# transponder-11_3_0.net
KiCad netlist of a schematic drawn in EAGLE
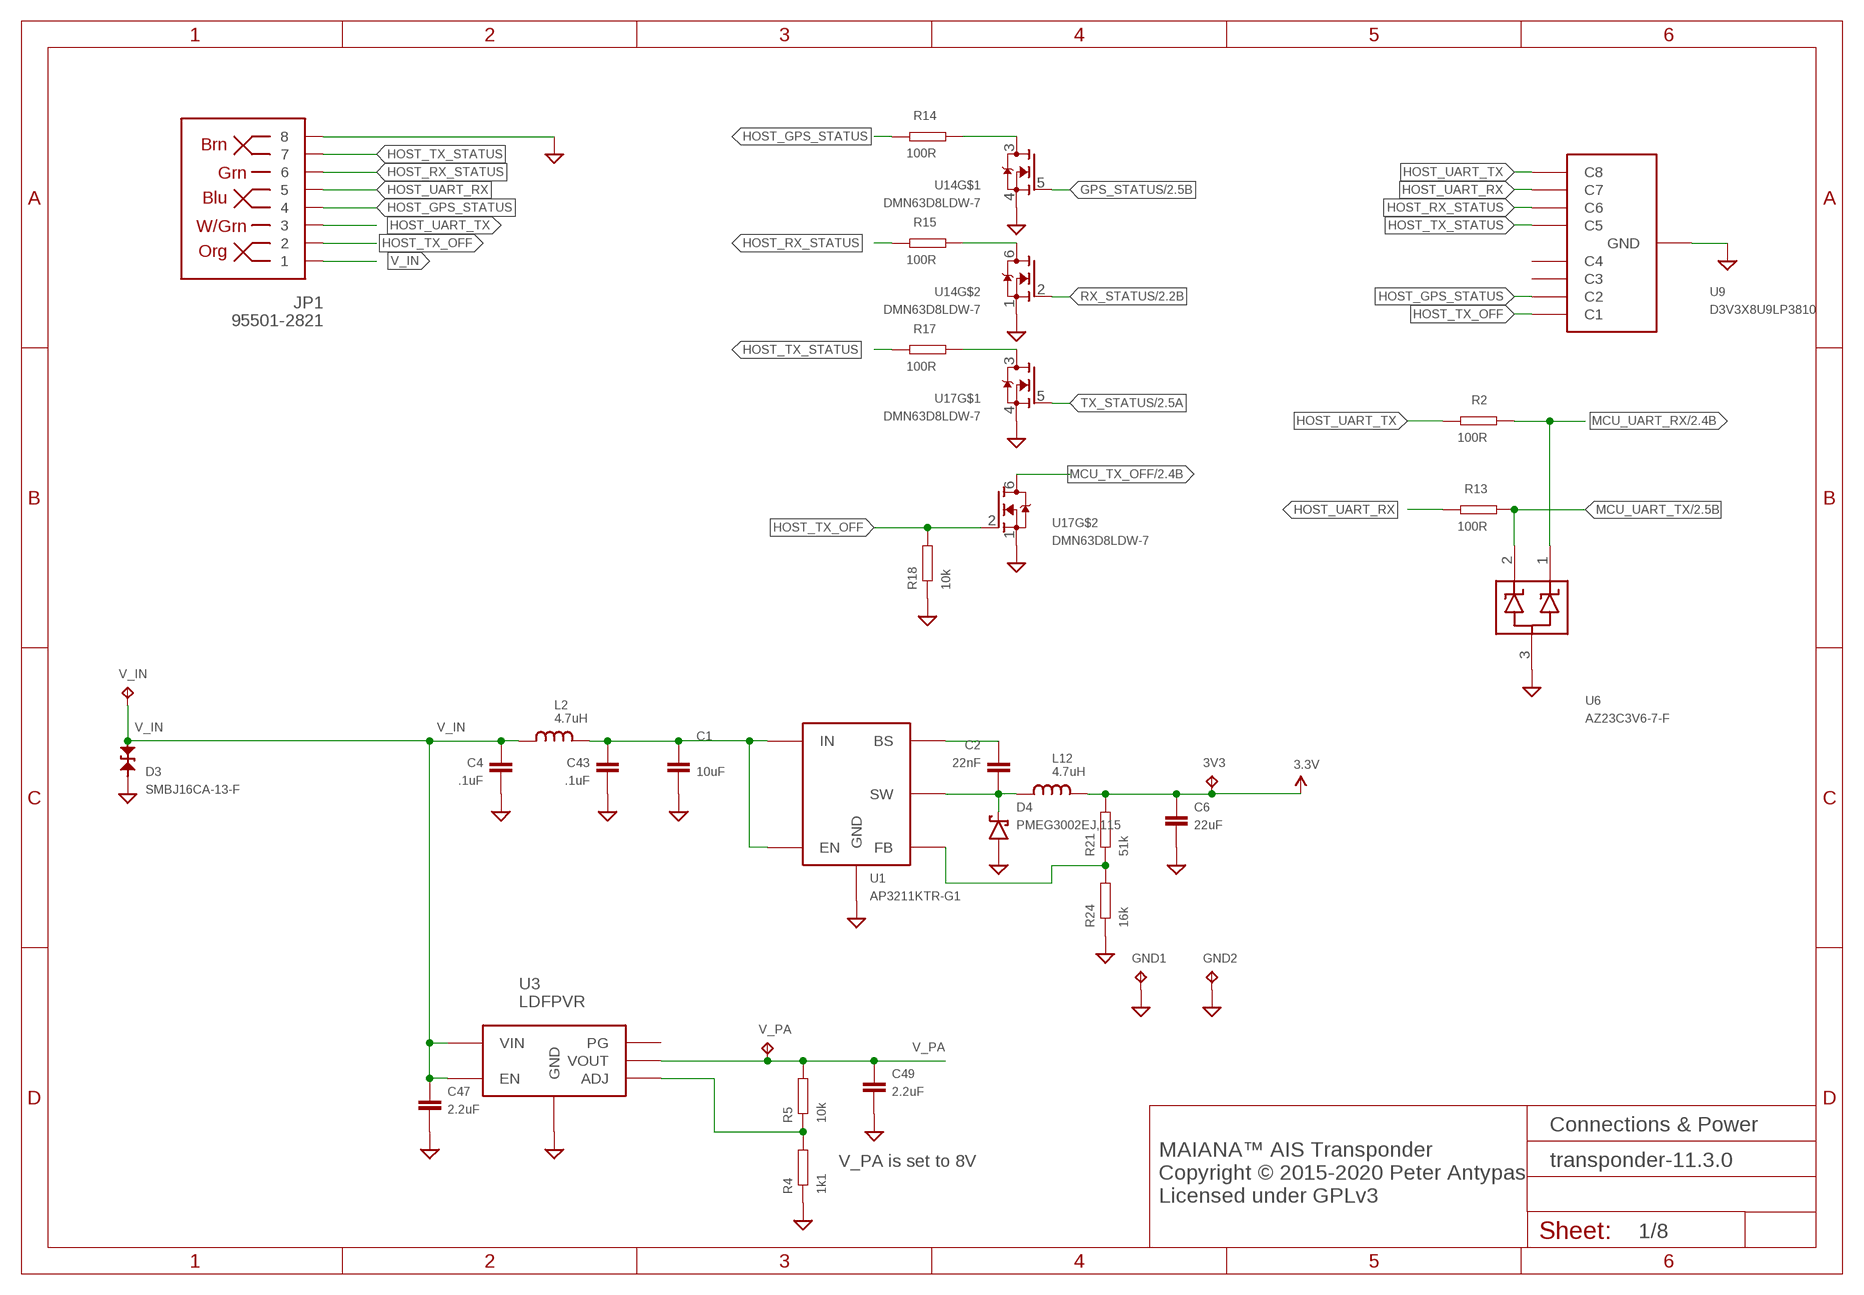
[diagram p0: schematic, sheet 1]
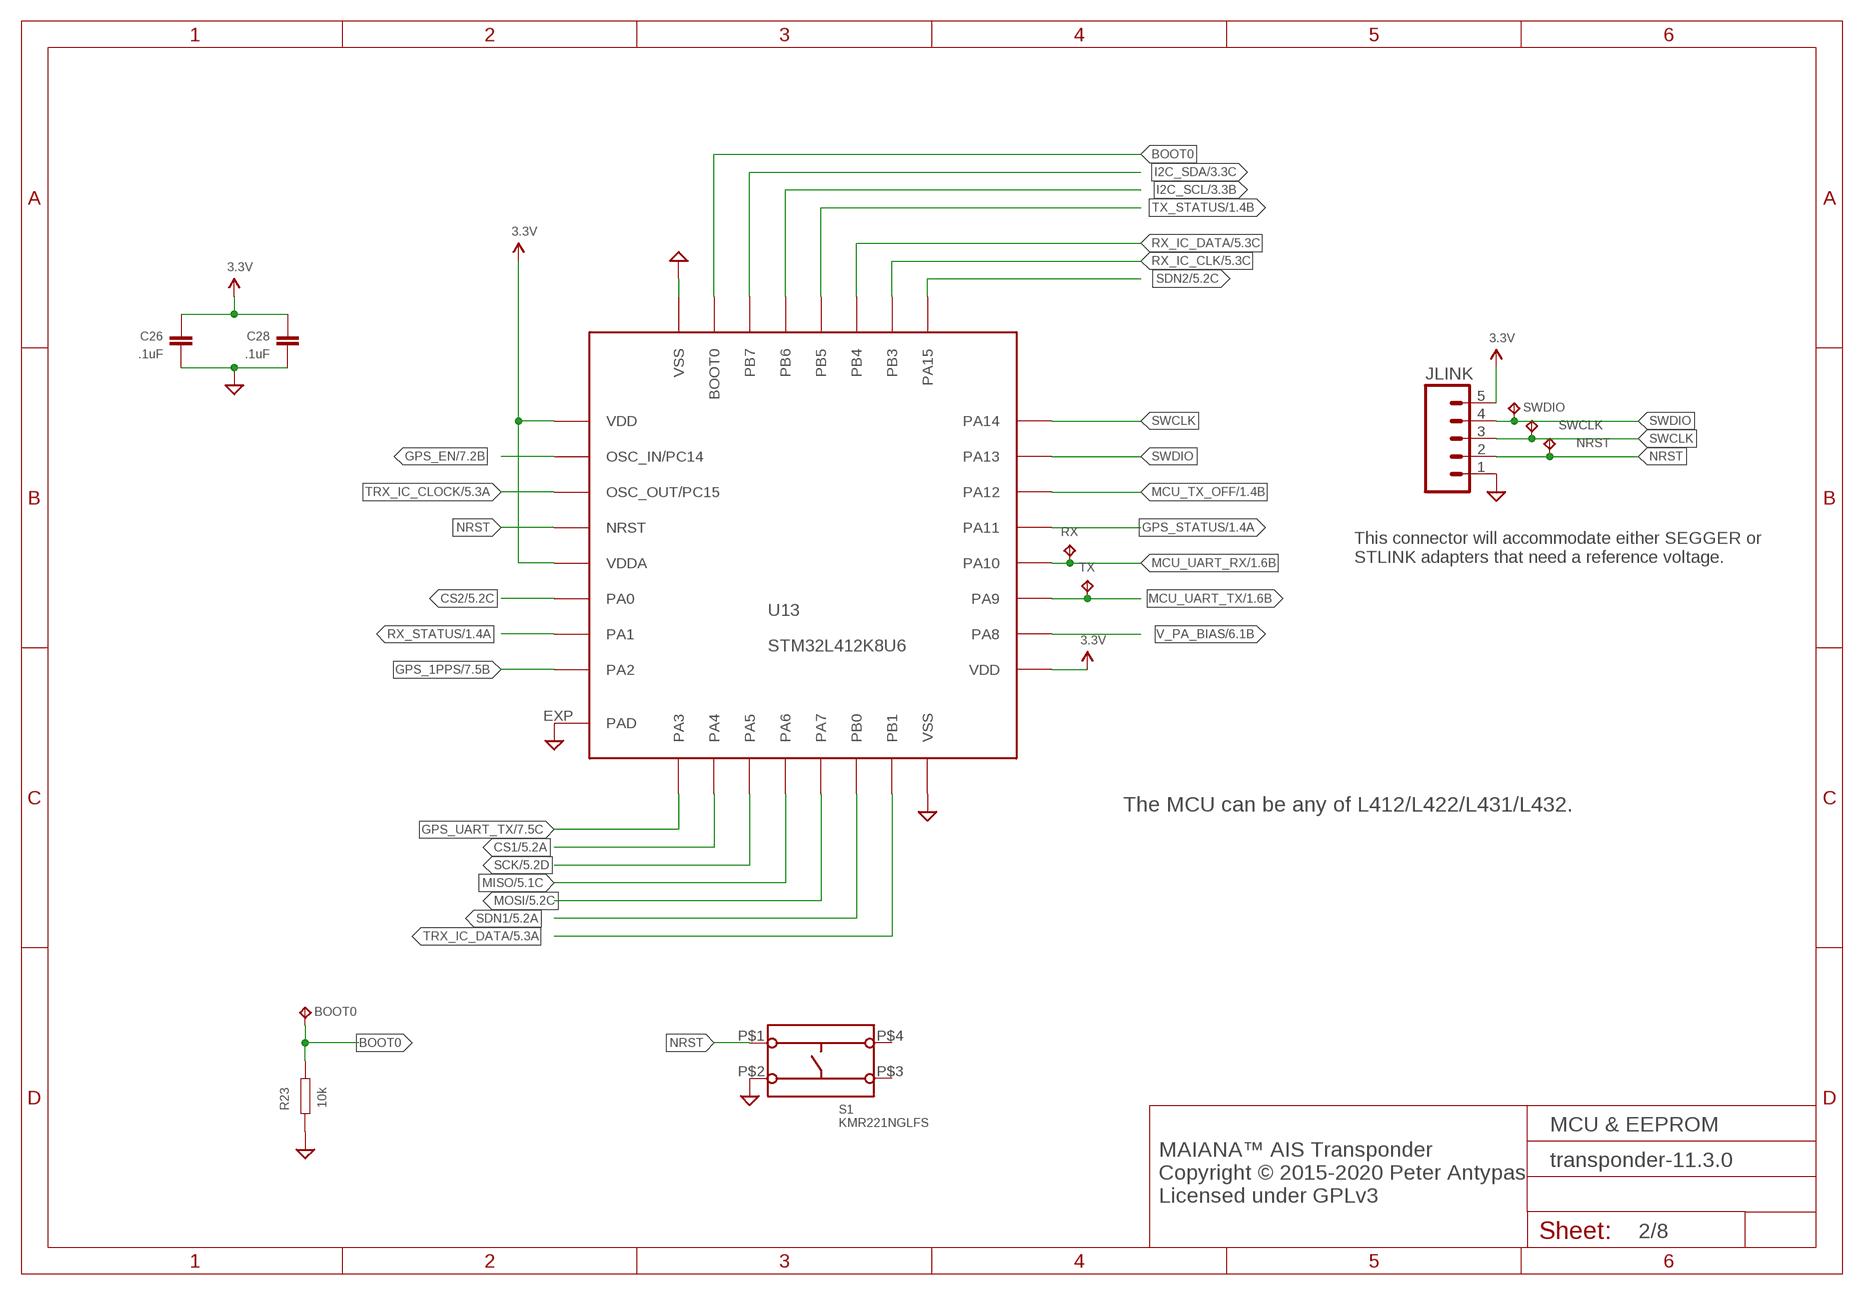
[diagram p1: schematic, sheet 2]
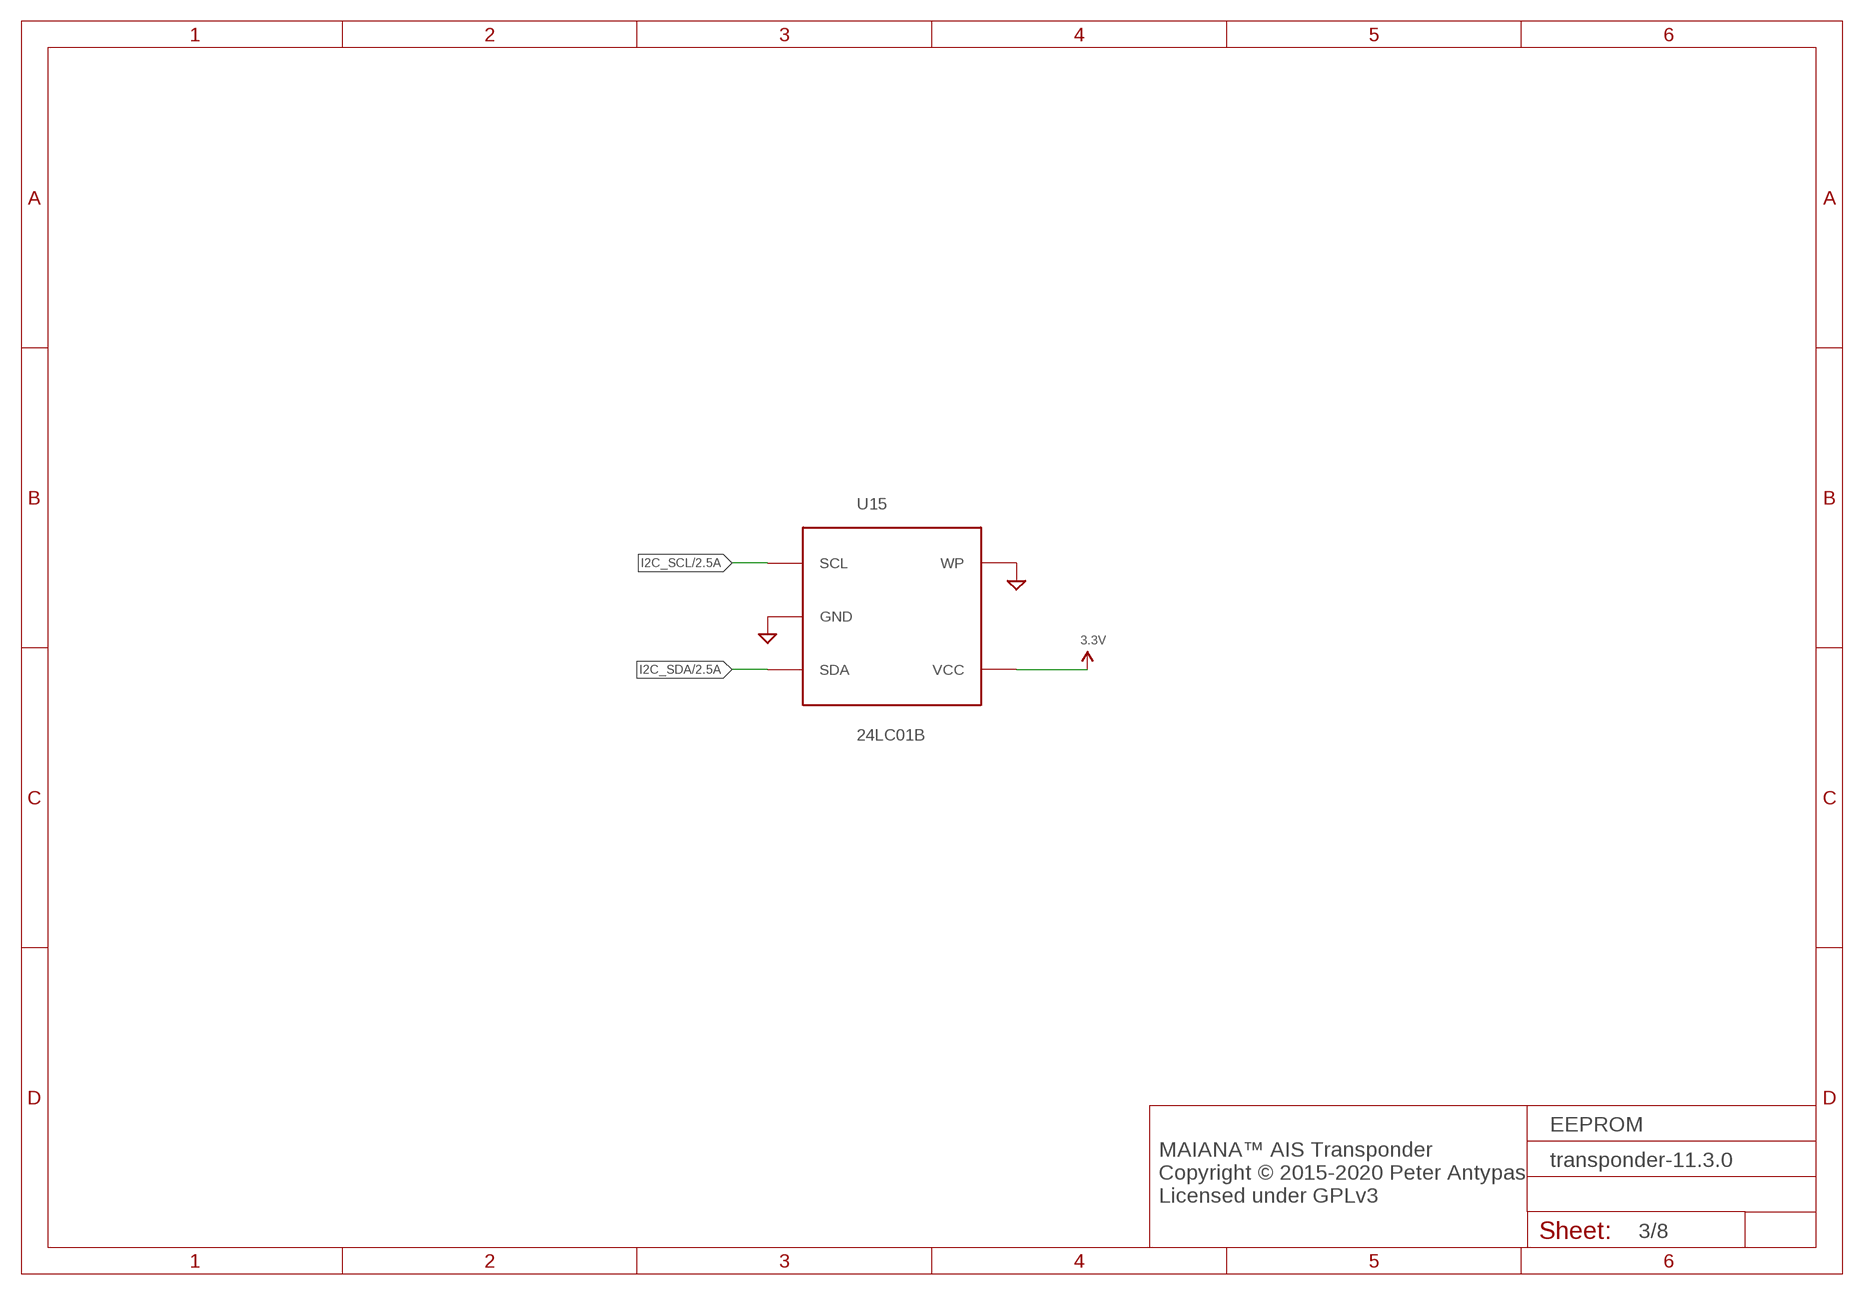
[diagram p2: schematic, sheet 3]
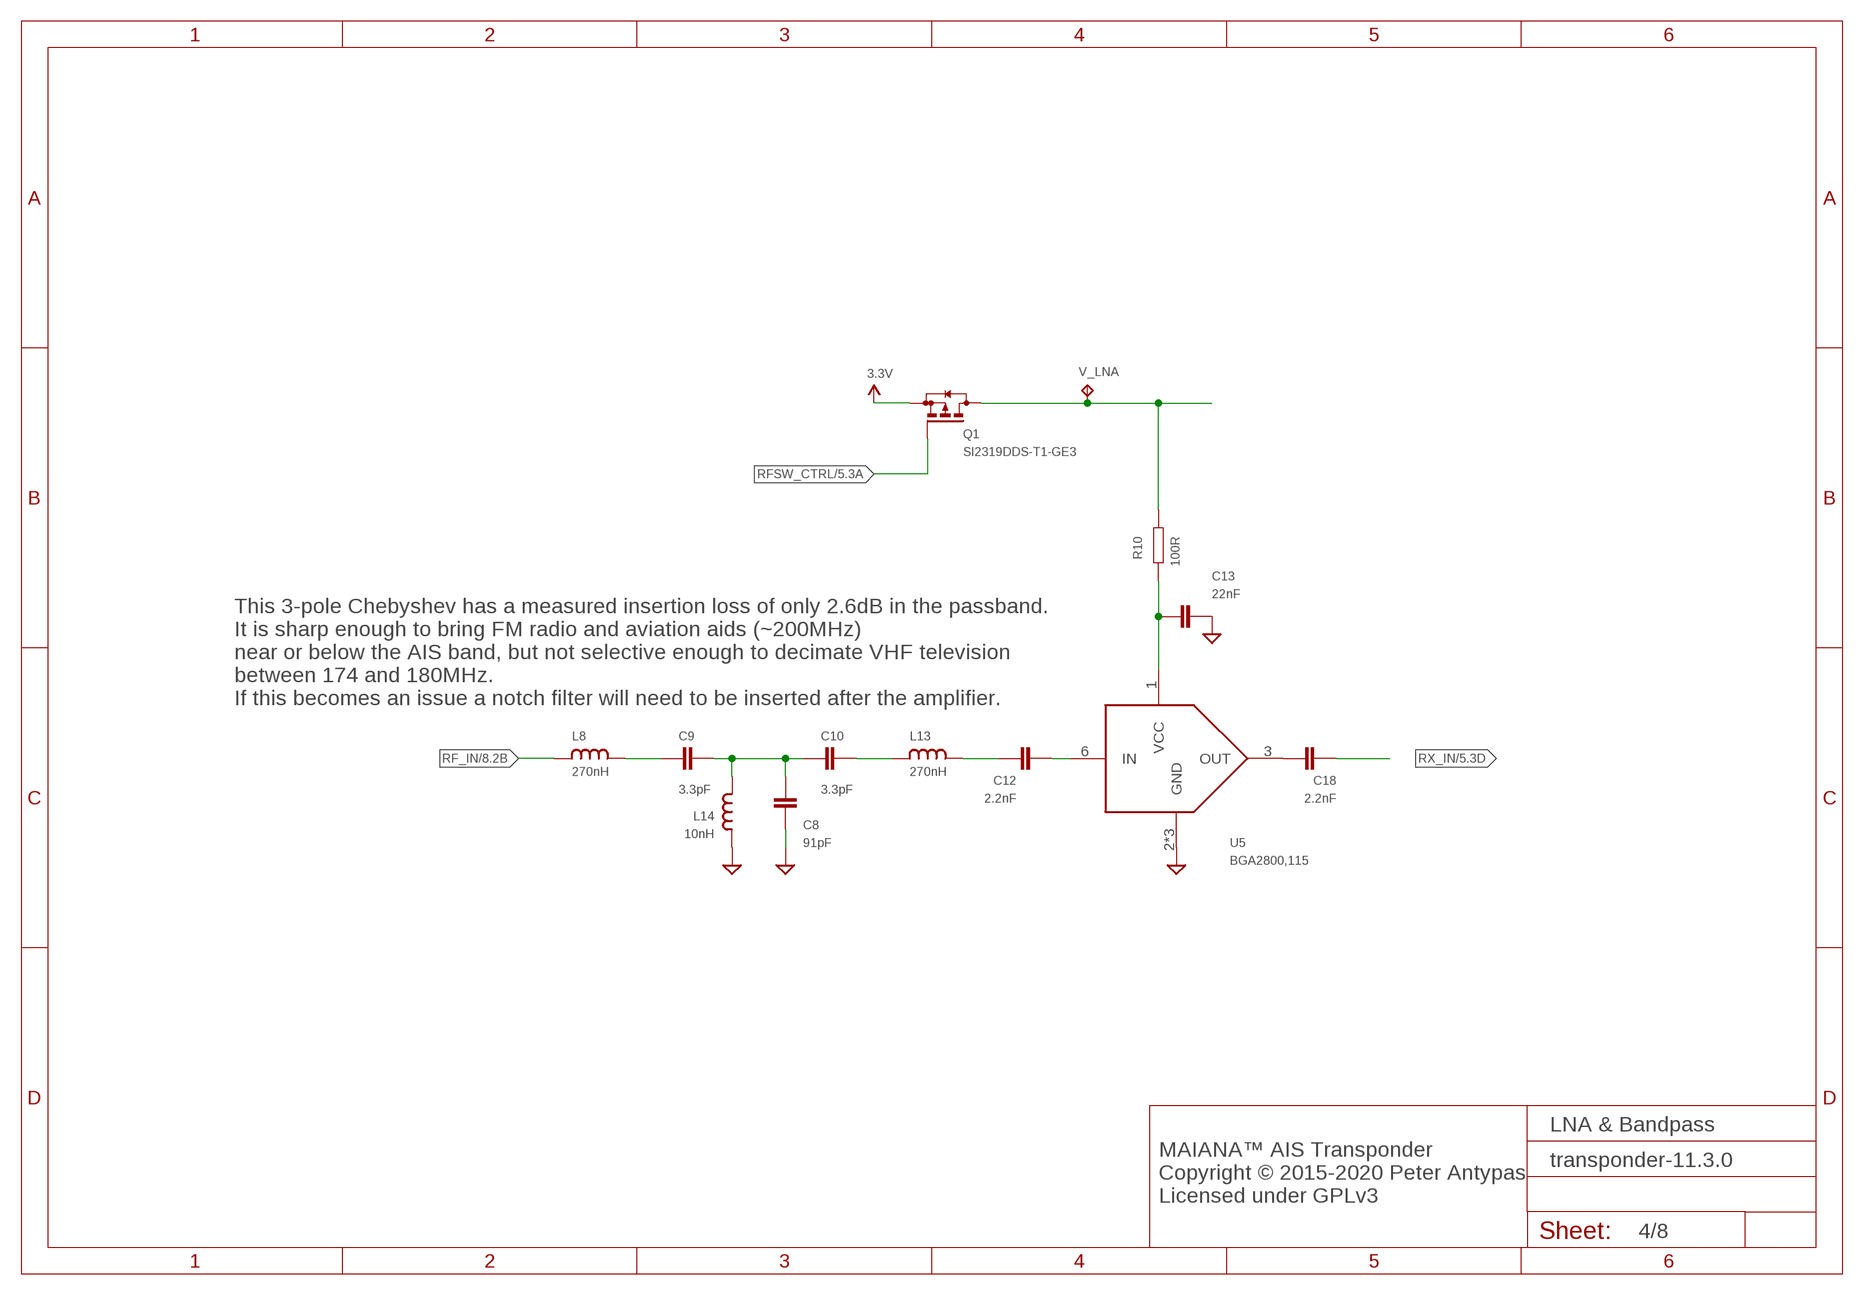
[diagram p3: schematic, sheet 4]
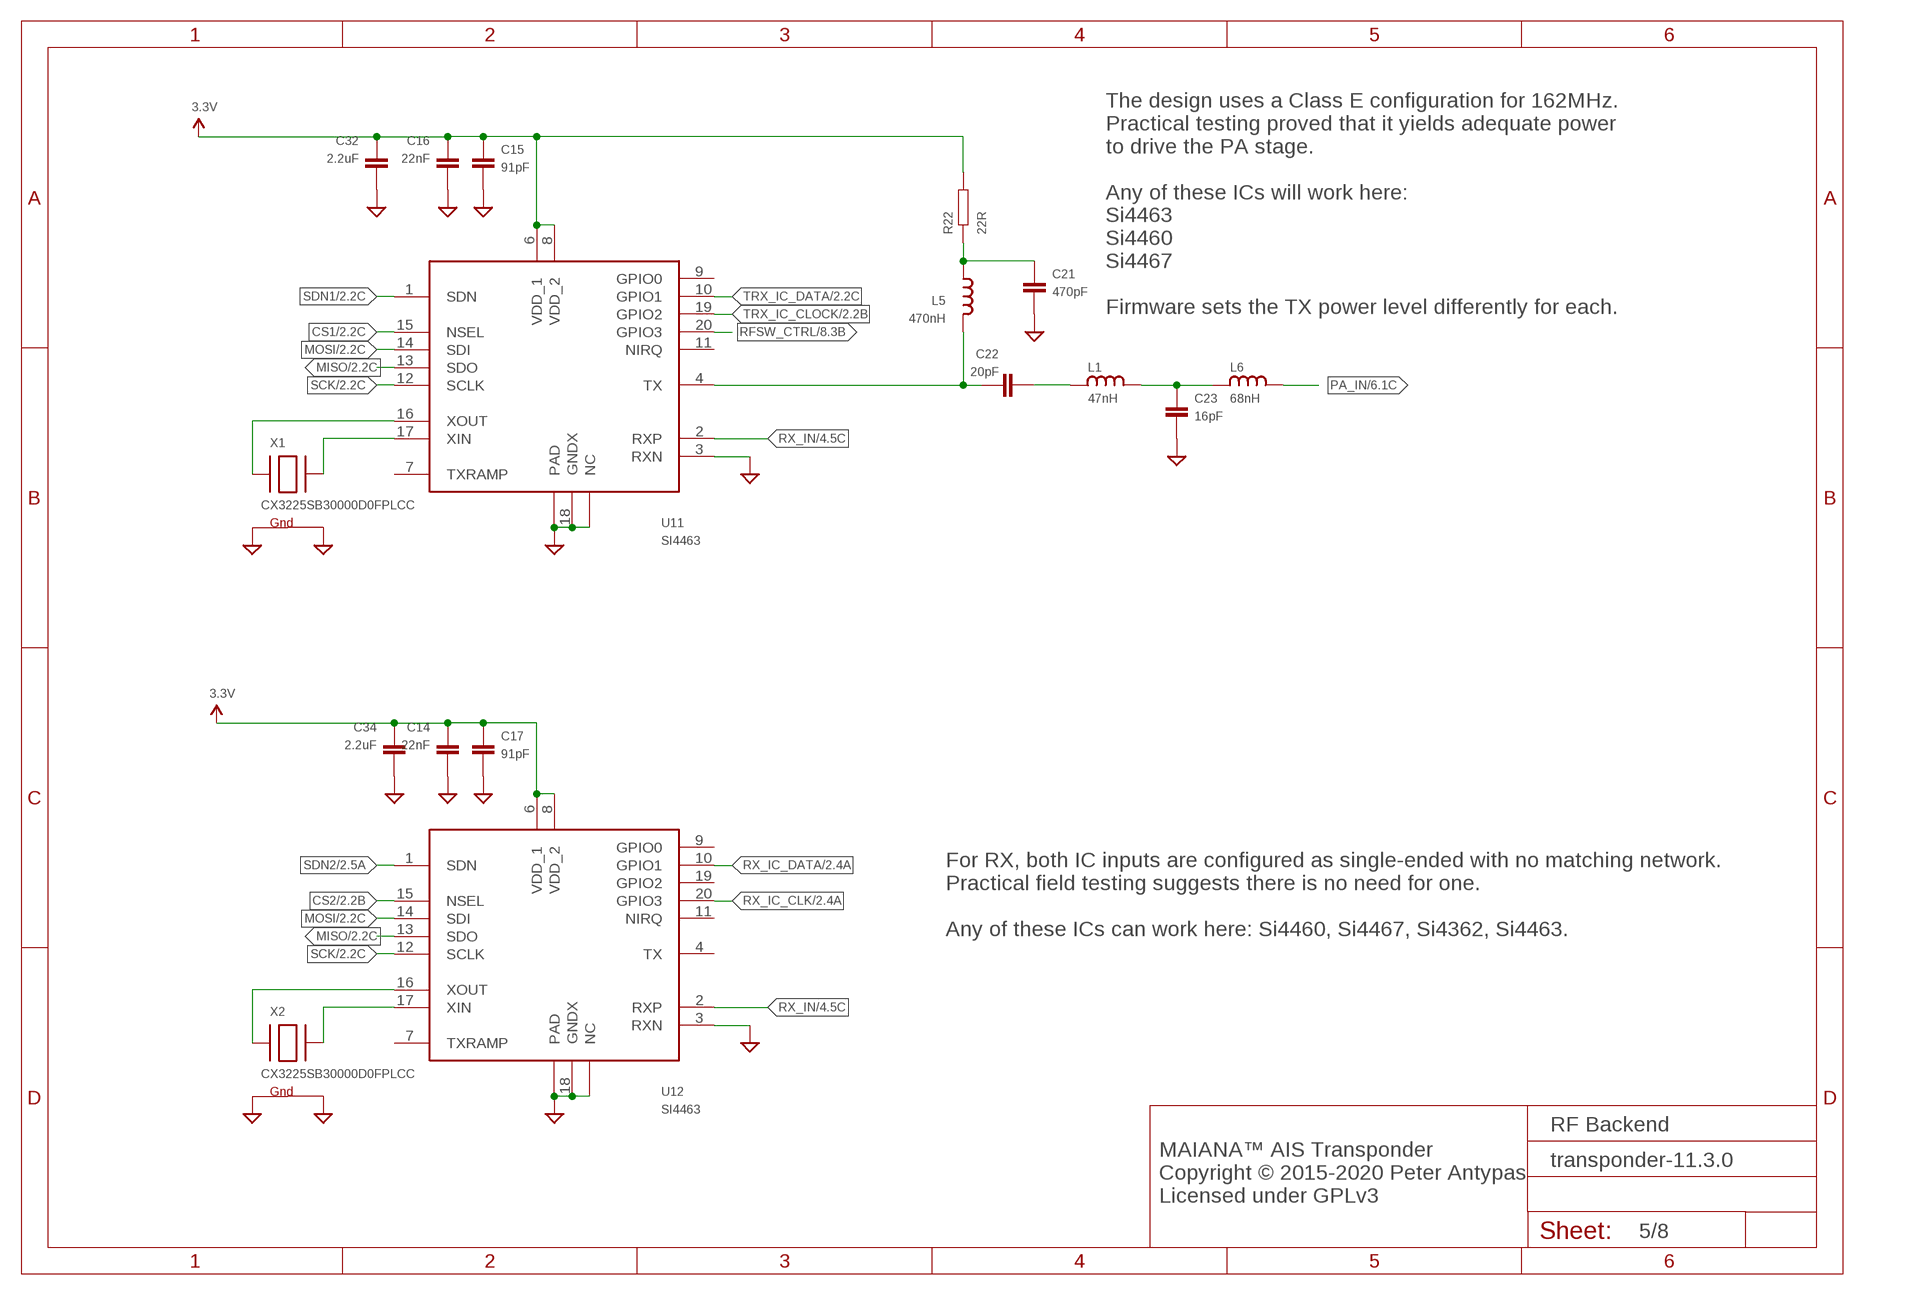
[diagram p4: schematic, sheet 5]
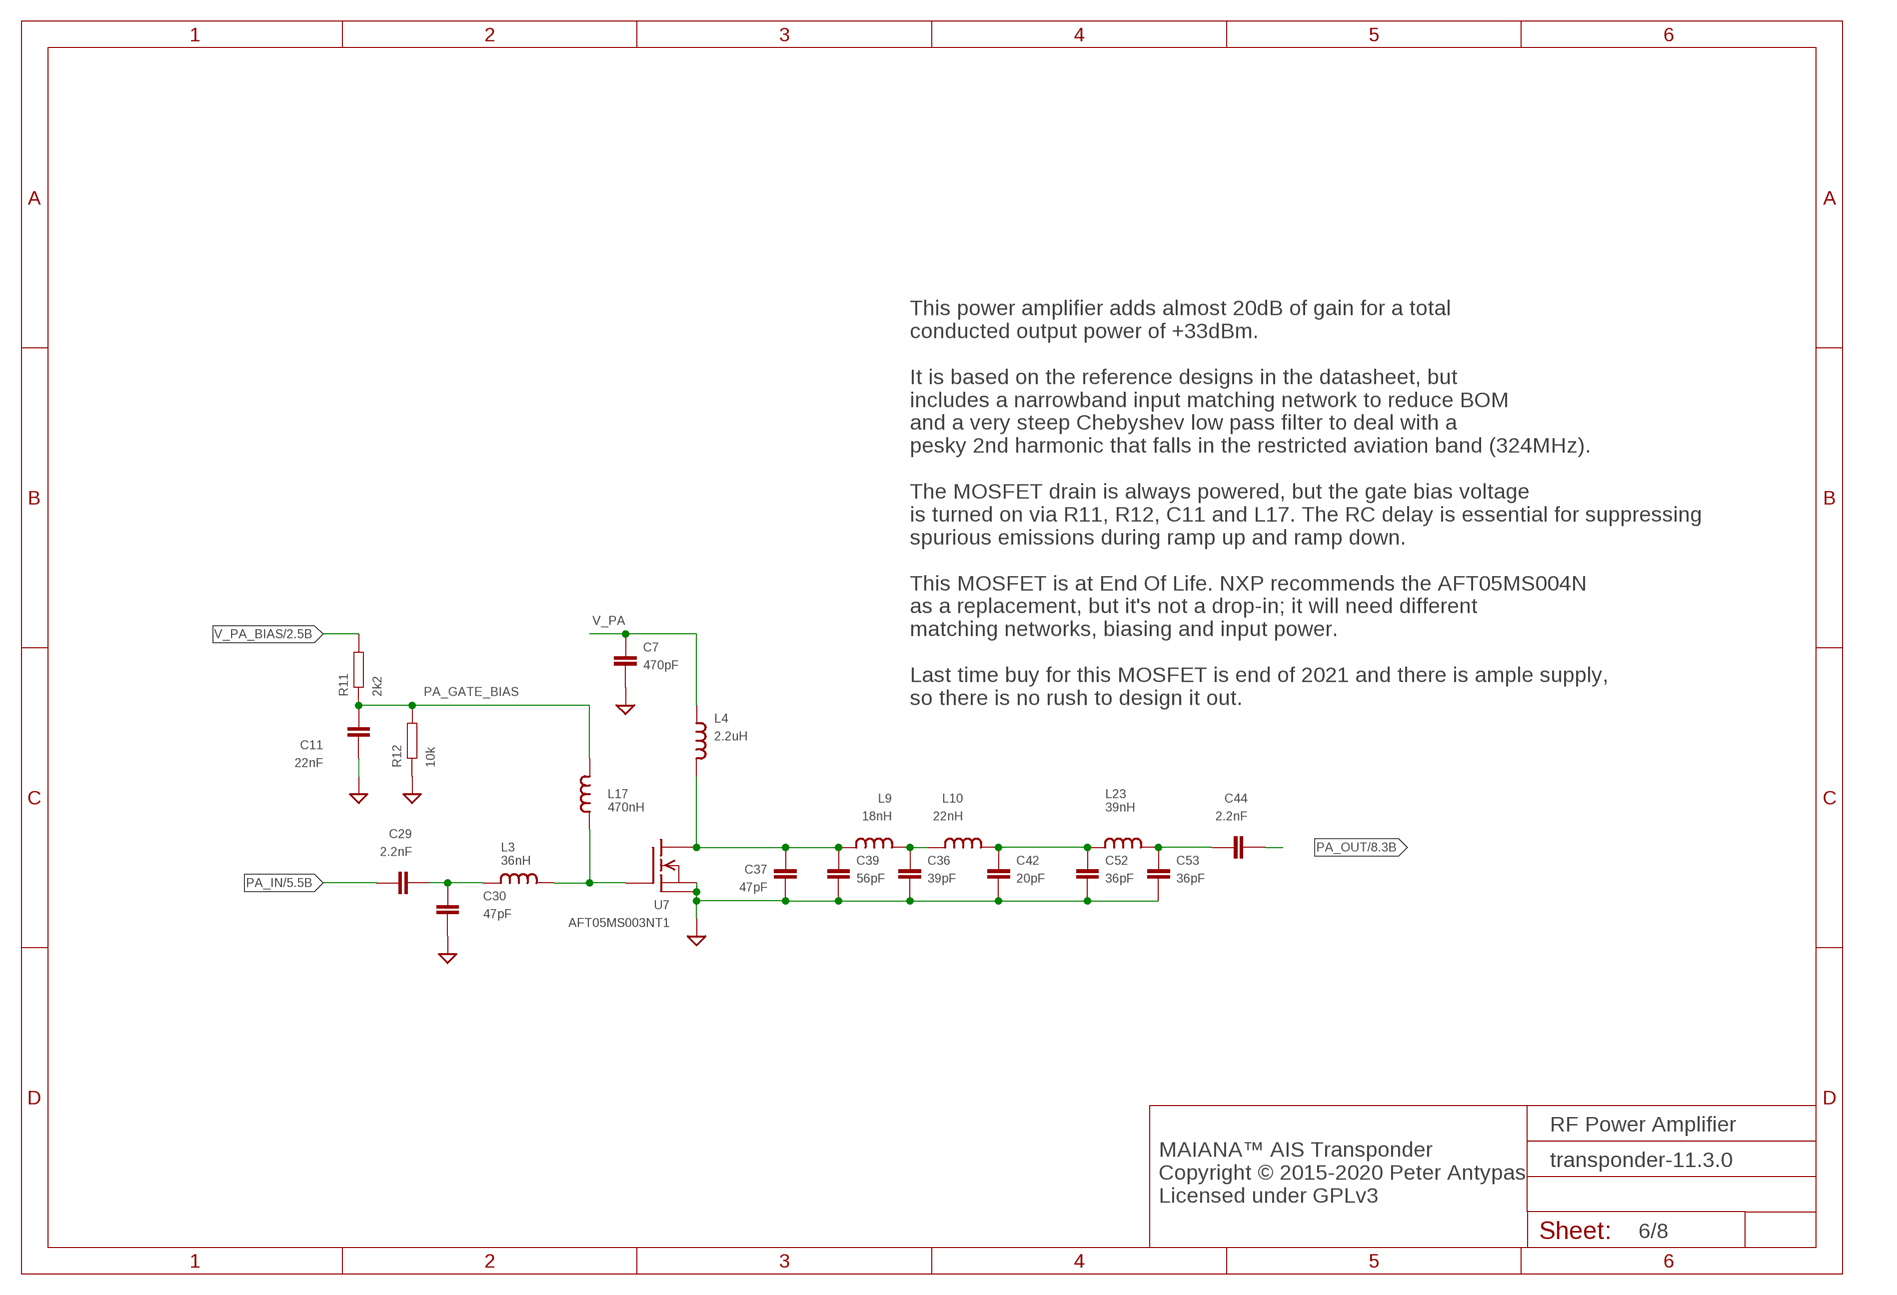
[diagram p5: schematic, sheet 6]
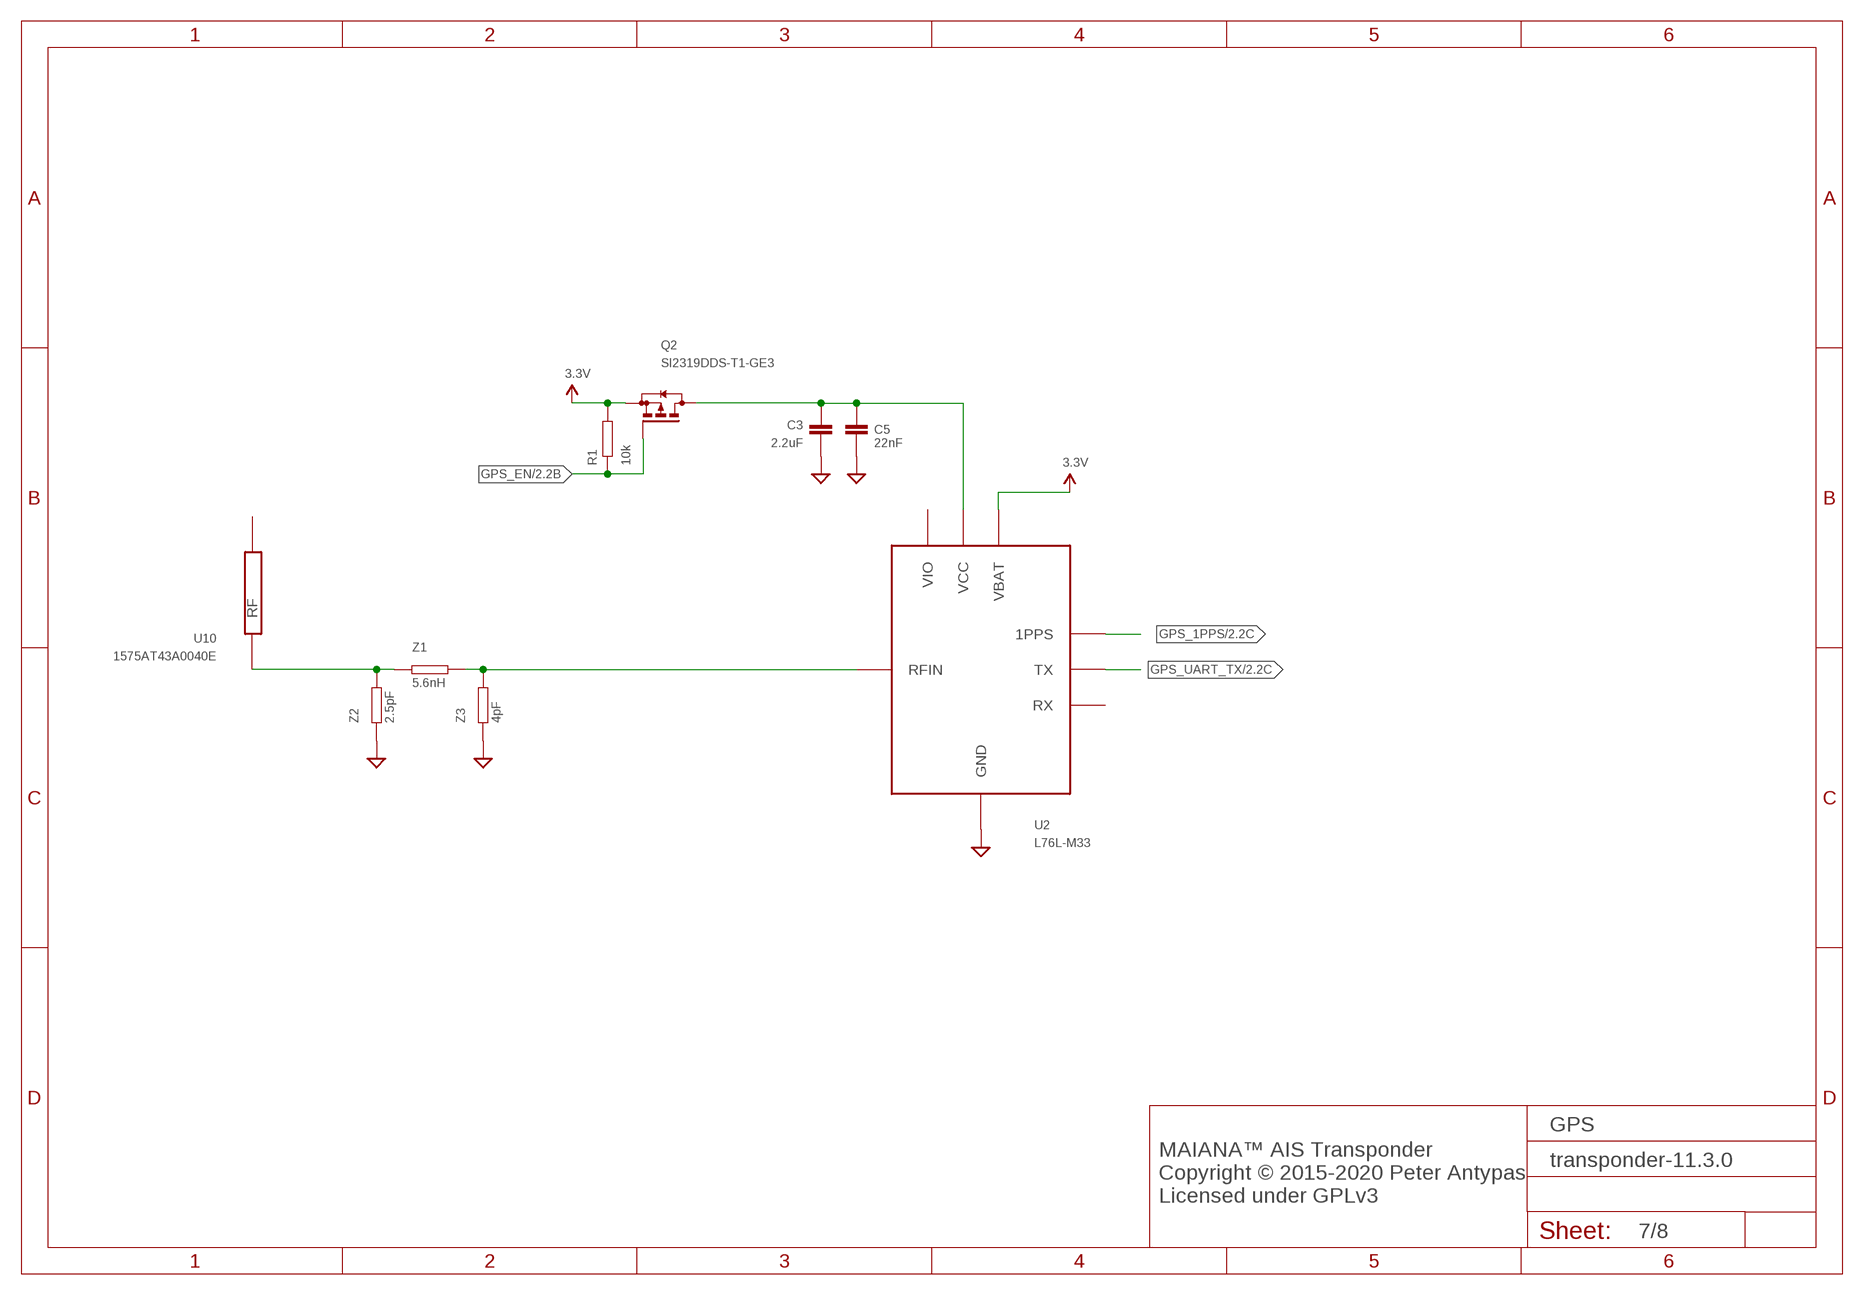
[diagram p6: schematic, sheet 7]
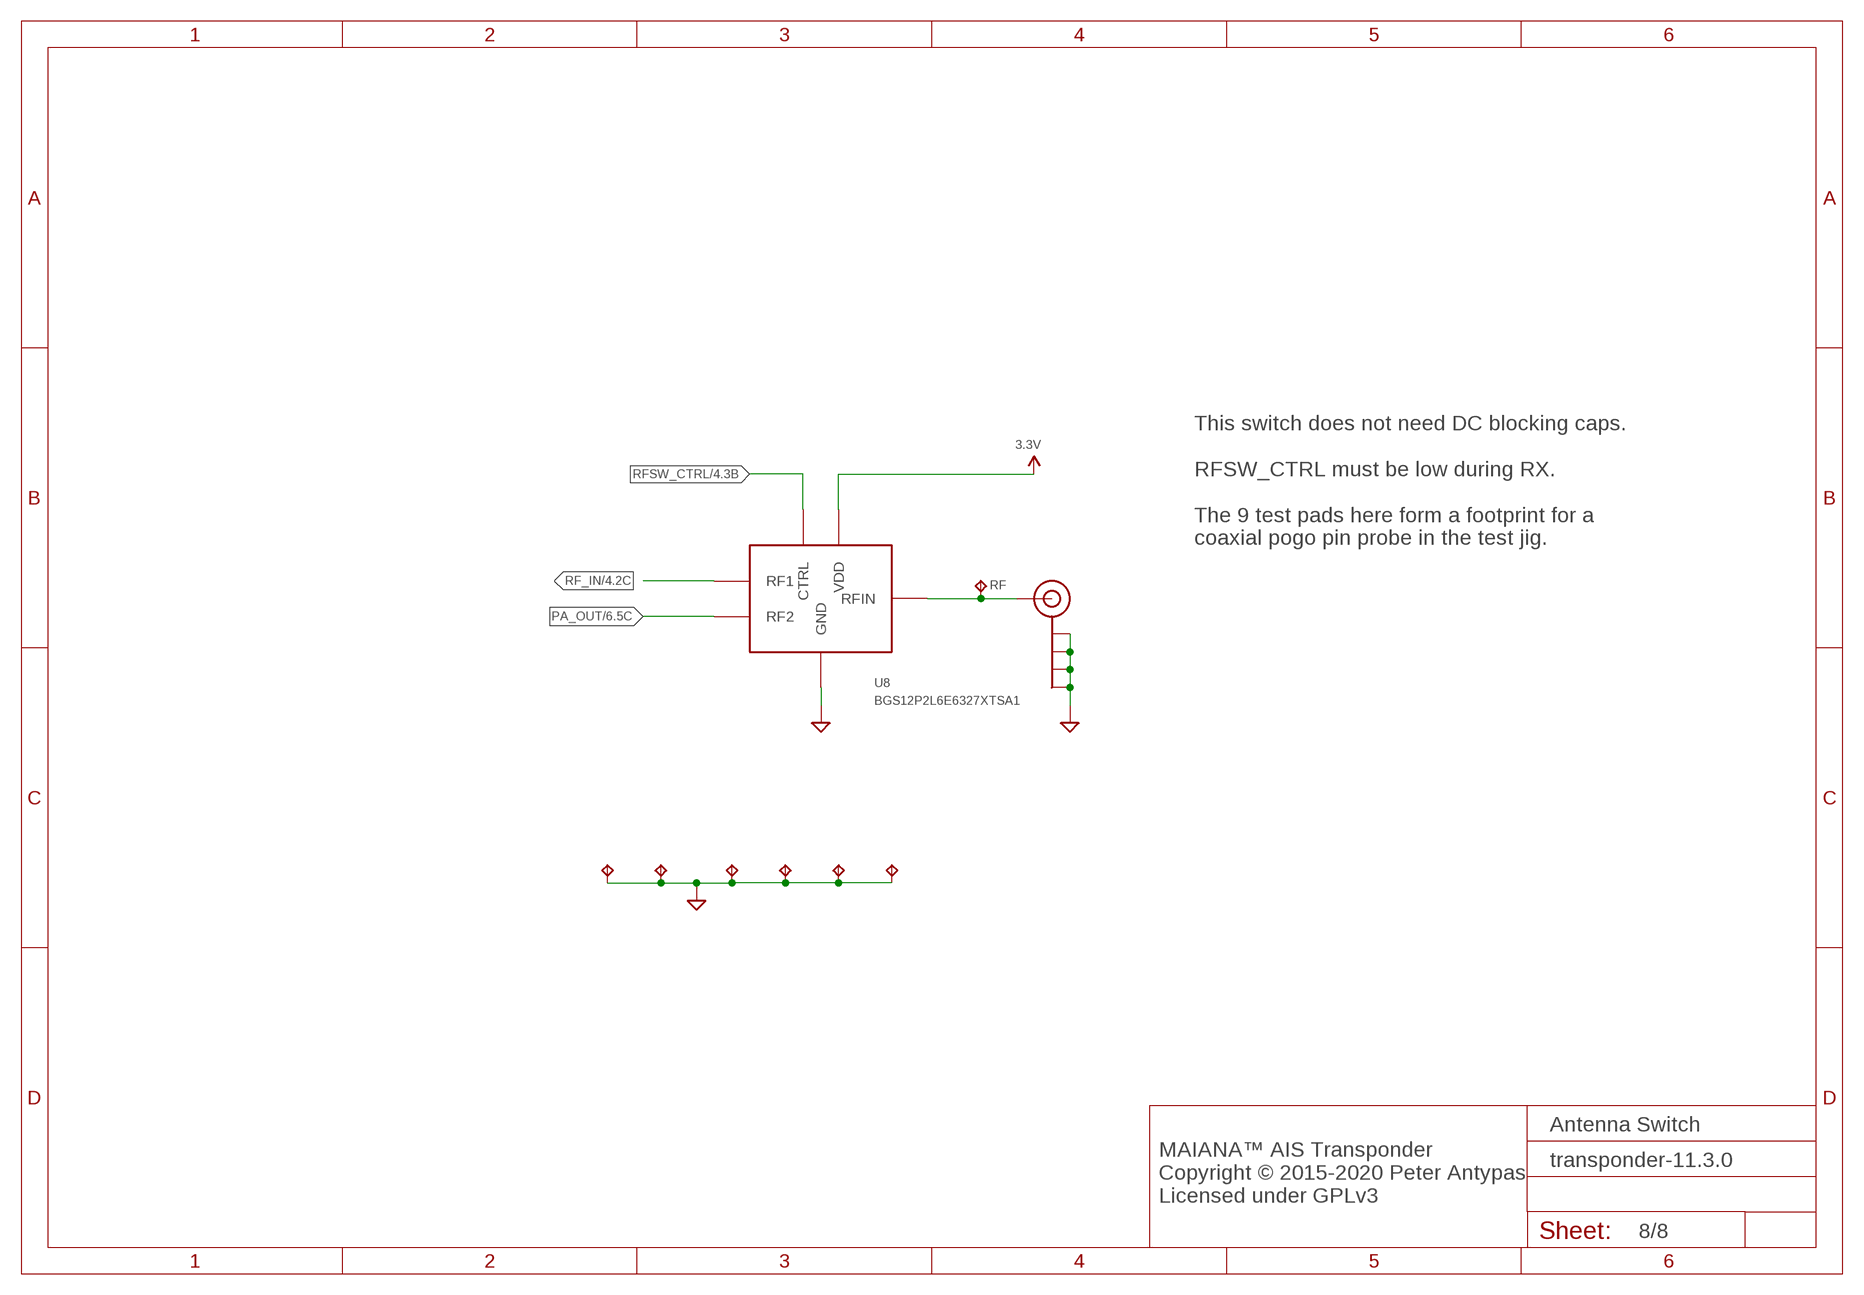
[diagram p7: schematic, sheet 8]

(export (version "E")
  (design (tool "Eeschema 10.0.6"))
  (components
    (comp (ref "3V3")
      (value "TPTP12R")
      (footprint "eagle-import:TP12R")
      (libsource (lib "eagle-import") (part "TPTP12R"))
    )
    (comp (ref "C1")
      (value "10uF")
      (footprint "eagle-import:0805")
      (fields (field (name "PARTNO") "EMK212ABJ106KG-T"))
      (libsource (lib "eagle-import") (part "CAPACITOR0805"))
    )
    (comp (ref "C2")
      (value "22nF")
      (footprint "eagle-import:0603")
      (fields (field (name "PARTNO") "GRM188R71E223KA01D"))
      (libsource (lib "eagle-import") (part "CAPACITOR0603"))
    )
    (comp (ref "C4")
      (value ".1uF")
      (footprint "eagle-import:0603")
      (fields (field (name "PARTNO") "EMK107B7104KAHT"))
      (libsource (lib "eagle-import") (part "CAPACITOR0603"))
    )
    (comp (ref "C6")
      (value "22uF")
      (footprint "eagle-import:0805")
      (libsource (lib "eagle-import") (part "CAPACITOR0805"))
    )
    (comp (ref "C43")
      (value ".1uF")
      (footprint "eagle-import:0603")
      (fields (field (name "PARTNO") "EMK107B7104KAHT"))
      (libsource (lib "eagle-import") (part "CAPACITOR0603"))
    )
    (comp (ref "C47")
      (value "2.2uF")
      (footprint "eagle-import:0603")
      (fields (field (name "PARTNO") "EMK107BJ225KA-T"))
      (libsource (lib "eagle-import") (part "CAPACITOR0603"))
    )
    (comp (ref "C49")
      (value "2.2uF")
      (footprint "eagle-import:0603")
      (fields (field (name "PARTNO") "EMK107BJ225KA-T"))
      (libsource (lib "eagle-import") (part "CAPACITOR0603"))
    )
    (comp (ref "D3")
      (value "SMBJ16CA-13-F")
      (footprint "eagle-import:SMB-BIDIR")
      (fields (field (name "PARTNO") "SMBJ16CA-13-F"))
      (libsource (lib "eagle-import") (part "DIODE-TVS-BIDIRSMB"))
    )
    (comp (ref "D4")
      (value "PMEG3002EJ,115")
      (footprint "eagle-import:SOD323")
      (fields (field (name "PARTNO") "NSR0240HT1G"))
      (libsource (lib "eagle-import") (part "DIODE-SCHOTTKYSOD323"))
    )
    (comp (ref "GND1")
      (value "TPTP12R")
      (footprint "eagle-import:TP12R")
      (libsource (lib "eagle-import") (part "TPTP12R"))
    )
    (comp (ref "GND2")
      (value "TPTP12R")
      (footprint "eagle-import:TP12R")
      (libsource (lib "eagle-import") (part "TPTP12R"))
    )
    (comp (ref "JP1")
      (value "95501-2821")
      (footprint "eagle-import:RJ45-8")
      (libsource (lib "eagle-import") (part "RJ45-8PTH"))
    )
    (comp (ref "L2")
      (value "4.7uH")
      (footprint "eagle-import:0805")
      (fields (field (name "PARTNO") "MLZ2012M4R7WT000"))
      (libsource (lib "eagle-import") (part "INDUCTOR0805"))
    )
    (comp (ref "L12")
      (value "4.7uH")
      (footprint "eagle-import:0805")
      (fields (field (name "PARTNO") "MLZ2012M4R7WT000"))
      (libsource (lib "eagle-import") (part "INDUCTOR0805"))
    )
    (comp (ref "R2")
      (value "100R")
      (footprint "eagle-import:0603")
      (libsource (lib "eagle-import") (part "RESISTOR0603"))
    )
    (comp (ref "R4")
      (value "1k1")
      (footprint "eagle-import:0603")
      (fields (field (name "PARTNO") "RC0603JR-071K1L"))
      (libsource (lib "eagle-import") (part "RESISTOR0603"))
    )
    (comp (ref "R5")
      (value "10k")
      (footprint "eagle-import:0603")
      (fields (field (name "PARTNO") "RC0603JR-0710KL"))
      (libsource (lib "eagle-import") (part "RESISTOR0603"))
    )
    (comp (ref "R13")
      (value "100R")
      (footprint "eagle-import:0603")
      (libsource (lib "eagle-import") (part "RESISTOR0603"))
    )
    (comp (ref "R14")
      (value "100R")
      (footprint "eagle-import:0603")
      (fields (field (name "PARTNO") "RC0603JR-07100RL"))
      (libsource (lib "eagle-import") (part "RESISTOR0603"))
    )
    (comp (ref "R15")
      (value "100R")
      (footprint "eagle-import:0603")
      (fields (field (name "PARTNO") "RC0603JR-07100RL"))
      (libsource (lib "eagle-import") (part "RESISTOR0603"))
    )
    (comp (ref "R17")
      (value "100R")
      (footprint "eagle-import:0603")
      (fields (field (name "PARTNO") "RC0603JR-070RL"))
      (libsource (lib "eagle-import") (part "RESISTOR0603"))
    )
    (comp (ref "R18")
      (value "10k")
      (footprint "eagle-import:0603")
      (fields (field (name "PARTNO") "RC0603JR-0710KL"))
      (libsource (lib "eagle-import") (part "RESISTOR0603"))
    )
    (comp (ref "R21")
      (value "51k")
      (footprint "eagle-import:0603")
      (fields (field (name "PARTNO") "RC0603JR-0751KL"))
      (libsource (lib "eagle-import") (part "RESISTOR0603"))
    )
    (comp (ref "R24")
      (value "16k")
      (footprint "eagle-import:0603")
      (fields (field (name "PARTNO") "RC0603FR-1016KL"))
      (libsource (lib "eagle-import") (part "RESISTOR0603"))
    )
    (comp (ref "U1")
      (value "AP3211KTR-G1")
      (footprint "eagle-import:SOT23-6")
      (libsource (lib "eagle-import") (part "AP3211"))
    )
    (comp (ref "U3")
      (value "LDFPVR")
      (footprint "eagle-import:DFN6-2X2")
      (libsource (lib "eagle-import") (part "LDFPVR"))
    )
    (comp (ref "U6")
      (value "AZ23C3V6-7-F")
      (footprint "eagle-import:SOT-23")
      (libsource (lib "eagle-import") (part "AZ23C3V6-7-F"))
    )
    (comp (ref "U9")
      (value "D3V3X8U9LP3810")
      (footprint "eagle-import:U-DFN3810-9(B)")
      (libsource (lib "eagle-import") (part "D3V3X8U9LP3810"))
    )
    (comp (ref "U14")
      (value "DMN63D8LDW-7")
      (footprint "eagle-import:SOT363")
      (fields (field (name "PARTNO") "DMN63D8LDW-7"))
      (libsource (lib "eagle-import") (part "DMN63D8LDW"))
    )
    (comp (ref "U17")
      (value "DMN63D8LDW-7")
      (footprint "eagle-import:SOT363")
      (fields (field (name "PARTNO") "DMN63D8LDW-7"))
      (libsource (lib "eagle-import") (part "DMN63D8LDW"))
    )
    (comp (ref "V_IN")
      (value "TPTP12R")
      (footprint "eagle-import:TP12R")
      (libsource (lib "eagle-import") (part "TPTP12R"))
    )
    (comp (ref "V_PA")
      (value "TPTP12R")
      (footprint "eagle-import:TP12R")
      (libsource (lib "eagle-import") (part "TPTP12R"))
    )
    (comp (ref "C8")
      (value "91pF")
      (footprint "eagle-import:0603")
      (fields (field (name "PARTNO") "GRM1885C2A910JA01D"))
      (libsource (lib "eagle-import") (part "CAPACITOR0603"))
    )
    (comp (ref "C9")
      (value "3.3pF")
      (footprint "eagle-import:0603")
      (fields (field (name "PARTNO") "GRM1885C1H3R3BA01D"))
      (libsource (lib "eagle-import") (part "CAPACITOR0603"))
    )
    (comp (ref "C10")
      (value "3.3pF")
      (footprint "eagle-import:0603")
      (fields (field (name "PARTNO") "GRM1885C1H3R3BA01D"))
      (libsource (lib "eagle-import") (part "CAPACITOR0603"))
    )
    (comp (ref "C12")
      (value "2.2nF")
      (footprint "eagle-import:0603")
      (fields (field (name "PARTNO") "GRM1885C1H222JA01J"))
      (libsource (lib "eagle-import") (part "CAPACITOR0603"))
    )
    (comp (ref "C13")
      (value "22nF")
      (footprint "eagle-import:0603")
      (fields (field (name "PARTNO") "GRM188R71E223KA01D"))
      (libsource (lib "eagle-import") (part "CAPACITOR0603"))
    )
    (comp (ref "C18")
      (value "2.2nF")
      (footprint "eagle-import:0603")
      (fields (field (name "PARTNO") "GRM1885C1H222JA01J"))
      (libsource (lib "eagle-import") (part "CAPACITOR0603"))
    )
    (comp (ref "L8")
      (value "270nH")
      (footprint "eagle-import:0603")
      (fields (field (name "PARTNO") "LQW18ANR27J00D"))
      (libsource (lib "eagle-import") (part "INDUCTOR0603"))
    )
    (comp (ref "L13")
      (value "270nH")
      (footprint "eagle-import:0603")
      (fields (field (name "PARTNO") "LQW18ANR27J00D"))
      (libsource (lib "eagle-import") (part "INDUCTOR0603"))
    )
    (comp (ref "L14")
      (value "10nH")
      (footprint "eagle-import:0603")
      (fields (field (name "PARTNO") "LQW18AN10NG00D"))
      (libsource (lib "eagle-import") (part "INDUCTOR0603"))
    )
    (comp (ref "Q1")
      (value "SI2319DDS-T1-GE3")
      (footprint "eagle-import:SOT23")
      (libsource (lib "eagle-import") (part "BSS84"))
    )
    (comp (ref "R10")
      (value "100R")
      (footprint "eagle-import:0603")
      (fields (field (name "PARTNO") "RC0603JR-07100RL"))
      (libsource (lib "eagle-import") (part "RESISTOR0603"))
    )
    (comp (ref "U5")
      (value "BGA2800,115")
      (footprint "eagle-import:SOT363")
      (libsource (lib "eagle-import") (part "BGA2870"))
    )
    (comp (ref "V_LNA")
      (value "TPTP12R")
      (footprint "eagle-import:TP12R")
      (libsource (lib "eagle-import") (part "TPTP12R"))
    )
    (comp (ref "C14")
      (value "22nF")
      (footprint "eagle-import:0603")
      (fields (field (name "PARTNO") "GRM188R71E223KA01D"))
      (libsource (lib "eagle-import") (part "CAPACITOR0603"))
    )
    (comp (ref "C15")
      (value "91pF")
      (footprint "eagle-import:0603")
      (fields (field (name "PARTNO") "GRM1885C2A910JA01D"))
      (libsource (lib "eagle-import") (part "CAPACITOR0603"))
    )
    (comp (ref "C16")
      (value "22nF")
      (footprint "eagle-import:0603")
      (fields (field (name "PARTNO") "GRM188R71E223KA01D"))
      (libsource (lib "eagle-import") (part "CAPACITOR0603"))
    )
    (comp (ref "C17")
      (value "91pF")
      (footprint "eagle-import:0603")
      (fields (field (name "PARTNO") "GRM1885C2A910JA01D"))
      (libsource (lib "eagle-import") (part "CAPACITOR0603"))
    )
    (comp (ref "C21")
      (value "470pF")
      (footprint "eagle-import:0603")
      (fields (field (name "PARTNO") "GRM1885C1H471JA01D"))
      (libsource (lib "eagle-import") (part "CAPACITOR0603"))
    )
    (comp (ref "C22")
      (value "20pF")
      (footprint "eagle-import:0603")
      (fields (field (name "PARTNO") "GRM1885C1H200JA01D"))
      (libsource (lib "eagle-import") (part "CAPACITOR0603"))
    )
    (comp (ref "C23")
      (value "16pF")
      (footprint "eagle-import:0603")
      (fields (field (name "PARTNO") "GCM1885C2A160JA16D"))
      (libsource (lib "eagle-import") (part "CAPACITOR0603"))
    )
    (comp (ref "C32")
      (value "2.2uF")
      (footprint "eagle-import:0603")
      (fields (field (name "PARTNO") "EMK107BJ225KA-T"))
      (libsource (lib "eagle-import") (part "CAPACITOR0603"))
    )
    (comp (ref "C34")
      (value "2.2uF")
      (footprint "eagle-import:0603")
      (fields (field (name "PARTNO") "EMK107BJ225KA-T"))
      (libsource (lib "eagle-import") (part "CAPACITOR0603"))
    )
    (comp (ref "L1")
      (value "47nH")
      (footprint "eagle-import:0603")
      (fields (field (name "PARTNO") "LQW18AN47NG00D"))
      (libsource (lib "eagle-import") (part "INDUCTOR0603"))
    )
    (comp (ref "L5")
      (value "470nH")
      (footprint "eagle-import:0603")
      (fields (field (name "PARTNO") "HK1608R47J-T"))
      (libsource (lib "eagle-import") (part "INDUCTOR0603"))
    )
    (comp (ref "L6")
      (value "68nH")
      (footprint "eagle-import:0603")
      (libsource (lib "eagle-import") (part "INDUCTOR0603"))
    )
    (comp (ref "R22")
      (value "22R")
      (footprint "eagle-import:0603")
      (fields (field (name "PARTNO") "RC0603JR-0722RL"))
      (libsource (lib "eagle-import") (part "RESISTOR0603"))
    )
    (comp (ref "U11")
      (value "SI4463")
      (footprint "eagle-import:SI4463")
      (fields (field (name "PARTNO") "SI4463-C2A-GMR"))
      (libsource (lib "eagle-import") (part "SI4463"))
    )
    (comp (ref "U12")
      (value "SI4463")
      (footprint "eagle-import:SI4463")
      (fields (field (name "PARTNO") "SI4463-C2A-GMR"))
      (libsource (lib "eagle-import") (part "SI4463"))
    )
    (comp (ref "X1")
      (value "CX3225SB30000D0FPLCC")
      (footprint "eagle-import:NX3225")
      (libsource (lib "eagle-import") (part "XTAL-4-3225"))
    )
    (comp (ref "X2")
      (value "CX3225SB30000D0FPLCC")
      (footprint "eagle-import:NX3225")
      (libsource (lib "eagle-import") (part "XTAL-4-3225"))
    )
    (comp (ref "J$1")
      (value "SMA_EDGE")
      (footprint "eagle-import:SMA-EDGE")
      (libsource (lib "eagle-import") (part "SMA_EDGE"))
    )
    (comp (ref "RF")
      (value "TPTP10R")
      (footprint "eagle-import:TP10R")
      (libsource (lib "eagle-import") (part "TPTP10R"))
    )
    (comp (ref "SWDIO1")
      (value "TPTP12R")
      (footprint "eagle-import:TP12R")
      (libsource (lib "eagle-import") (part "TPTP12R"))
    )
    (comp (ref "SWDIO2")
      (value "TPTP12R")
      (footprint "eagle-import:TP12R")
      (libsource (lib "eagle-import") (part "TPTP12R"))
    )
    (comp (ref "SWDIO3")
      (value "TPTP12R")
      (footprint "eagle-import:TP12R")
      (libsource (lib "eagle-import") (part "TPTP12R"))
    )
    (comp (ref "SWDIO4")
      (value "TPTP12R")
      (footprint "eagle-import:TP12R")
      (libsource (lib "eagle-import") (part "TPTP12R"))
    )
    (comp (ref "SWDIO5")
      (value "TPTP12R")
      (footprint "eagle-import:TP12R")
      (libsource (lib "eagle-import") (part "TPTP12R"))
    )
    (comp (ref "SWDIO6")
      (value "TPTP12R")
      (footprint "eagle-import:TP12R")
      (libsource (lib "eagle-import") (part "TPTP12R"))
    )
    (comp (ref "U8")
      (value "BGS12P2L6E6327XTSA1")
      (footprint "eagle-import:PSON50P145X100X50-6N")
      (fields (field (name "PARTNO") "BGS12PL6") (field (name "PARTNO_1") "‎BGS12P2L6E6327XTSA1‎"))
      (libsource (lib "eagle-import") (part "BGS12PL6"))
    )
    (comp (ref "BOOT0")
      (value "TPTP12R")
      (footprint "eagle-import:TP12R")
      (libsource (lib "eagle-import") (part "TPTP12R"))
    )
    (comp (ref "C26")
      (value ".1uF")
      (footprint "eagle-import:0603")
      (fields (field (name "PARTNO") "EMK107B7104KAHT"))
      (libsource (lib "eagle-import") (part "CAPACITOR0603"))
    )
    (comp (ref "C28")
      (value ".1uF")
      (footprint "eagle-import:0603")
      (fields (field (name "PARTNO") "EMK107B7104KAHT"))
      (libsource (lib "eagle-import") (part "CAPACITOR0603"))
    )
    (comp (ref "JLINK")
      (value "M05PTH")
      (footprint "eagle-import:1X05")
      (libsource (lib "eagle-import") (part "M05PTH"))
    )
    (comp (ref "NRST")
      (value "TPTP12R")
      (footprint "eagle-import:TP12R")
      (libsource (lib "eagle-import") (part "TPTP12R"))
    )
    (comp (ref "R23")
      (value "10k")
      (footprint "eagle-import:0603")
      (fields (field (name "PARTNO") "RC0603JR-0710KL"))
      (libsource (lib "eagle-import") (part "RESISTOR0603"))
    )
    (comp (ref "RX")
      (value "TPTP12R")
      (footprint "eagle-import:TP12R")
      (libsource (lib "eagle-import") (part "TPTP12R"))
    )
    (comp (ref "S1")
      (value "KMR221NGLFS")
      (footprint "eagle-import:KMR221NGLFS")
      (libsource (lib "eagle-import") (part "KMR221NGLFS"))
    )
    (comp (ref "SWCLK")
      (value "TPTP12R")
      (footprint "eagle-import:TP12R")
      (libsource (lib "eagle-import") (part "TPTP12R"))
    )
    (comp (ref "SWDIO")
      (value "TPTP12R")
      (footprint "eagle-import:TP12R")
      (libsource (lib "eagle-import") (part "TPTP12R"))
    )
    (comp (ref "TX")
      (value "TPTP12R")
      (footprint "eagle-import:TP12R")
      (libsource (lib "eagle-import") (part "TPTP12R"))
    )
    (comp (ref "U13")
      (value "STM32L412K8U6")
      (footprint "eagle-import:QFN32")
      (libsource (lib "eagle-import") (part "STM32L432KXXX"))
    )
    (comp (ref "U15")
      (value "24LC01B")
      (footprint "eagle-import:SOT23-5")
      (libsource (lib "eagle-import") (part "24LC01B"))
    )
    (comp (ref "C7")
      (value "470pF")
      (footprint "eagle-import:0603")
      (fields (field (name "PARTNO") "GRM1885C1H471JA01D"))
      (libsource (lib "eagle-import") (part "CAPACITOR0603"))
    )
    (comp (ref "C11")
      (value "22nF")
      (footprint "eagle-import:0603")
      (fields (field (name "PARTNO") "GRM188R71E223KA01D"))
      (libsource (lib "eagle-import") (part "CAPACITOR0603"))
    )
    (comp (ref "C29")
      (value "2.2nF")
      (footprint "eagle-import:0603")
      (fields (field (name "PARTNO") "GRM1885C1H222JA01J"))
      (libsource (lib "eagle-import") (part "CAPACITOR0603"))
    )
    (comp (ref "C30")
      (value "47pF")
      (footprint "eagle-import:0603")
      (fields (field (name "PARTNO") "GRM1885C1H470JA01J"))
      (libsource (lib "eagle-import") (part "CAPACITOR0603"))
    )
    (comp (ref "C36")
      (value "39pF")
      (footprint "eagle-import:0603")
      (fields (field (name "PARTNO") "GRM1885C1H390JA01D"))
      (libsource (lib "eagle-import") (part "CAPACITOR0603"))
    )
    (comp (ref "C37")
      (value "47pF")
      (footprint "eagle-import:0603")
      (fields (field (name "PARTNO") "GRM1885C1H470JA01J"))
      (libsource (lib "eagle-import") (part "CAPACITOR0603"))
    )
    (comp (ref "C39")
      (value "56pF")
      (footprint "eagle-import:0603")
      (fields (field (name "PARTNO") "GRM1885C1H560JA01D"))
      (libsource (lib "eagle-import") (part "CAPACITOR0603"))
    )
    (comp (ref "C42")
      (value "20pF")
      (footprint "eagle-import:0603")
      (fields (field (name "PARTNO") "GRM1885C1H200JA01D"))
      (libsource (lib "eagle-import") (part "CAPACITOR0603"))
    )
    (comp (ref "C44")
      (value "2.2nF")
      (footprint "eagle-import:0603")
      (fields (field (name "PARTNO") "GRM1885C1H222JA01J"))
      (libsource (lib "eagle-import") (part "CAPACITOR0603"))
    )
    (comp (ref "C52")
      (value "36pF")
      (footprint "eagle-import:0603")
      (fields (field (name "PARTNO") "06035A360JAT2A"))
      (libsource (lib "eagle-import") (part "CAPACITOR0603"))
    )
    (comp (ref "C53")
      (value "36pF")
      (footprint "eagle-import:0603")
      (fields (field (name "PARTNO") "06035A360JAT2A"))
      (libsource (lib "eagle-import") (part "CAPACITOR0603"))
    )
    (comp (ref "L3")
      (value "36nH")
      (footprint "eagle-import:0603")
      (fields (field (name "PARTNO") "LQW18AN36NG00D"))
      (libsource (lib "eagle-import") (part "INDUCTOR0603"))
    )
    (comp (ref "L4")
      (value "2.2uH")
      (footprint "eagle-import:0805")
      (fields (field (name "PARTNO") "BRC2012T2R2MD"))
      (libsource (lib "eagle-import") (part "INDUCTOR0805"))
    )
    (comp (ref "L9")
      (value "18nH")
      (footprint "eagle-import:0603")
      (fields (field (name "PARTNO") "LQW18AN18NG00D"))
      (libsource (lib "eagle-import") (part "INDUCTOR0603"))
    )
    (comp (ref "L10")
      (value "22nH")
      (footprint "eagle-import:0603")
      (fields (field (name "PARTNO") "LQW18AN22NJ00D"))
      (libsource (lib "eagle-import") (part "INDUCTOR0603"))
    )
    (comp (ref "L17")
      (value "470nH")
      (footprint "eagle-import:0603")
      (fields (field (name "PARTNO") "HK1608R47J-T"))
      (libsource (lib "eagle-import") (part "INDUCTOR0603"))
    )
    (comp (ref "L23")
      (value "39nH")
      (footprint "eagle-import:0603")
      (fields (field (name "PARTNO") "LQW18AN39NG00D"))
      (libsource (lib "eagle-import") (part "INDUCTOR0603"))
    )
    (comp (ref "R11")
      (value "2k2")
      (footprint "eagle-import:0603")
      (fields (field (name "PARTNO") "RC0603FR-072K2L"))
      (libsource (lib "eagle-import") (part "RESISTOR0603"))
    )
    (comp (ref "R12")
      (value "10k")
      (footprint "eagle-import:0603")
      (fields (field (name "PARTNO") "RC0603JR-0710KL"))
      (libsource (lib "eagle-import") (part "RESISTOR0603"))
    )
    (comp (ref "U7")
      (value "AFT05MS003NT1")
      (footprint "eagle-import:SOT-89")
      (libsource (lib "eagle-import") (part "AFT0SMS003N"))
    )
    (comp (ref "C3")
      (value "2.2uF")
      (footprint "eagle-import:0603")
      (fields (field (name "PARTNO") "EMK107BJ225KA-T"))
      (libsource (lib "eagle-import") (part "CAPACITOR0603"))
    )
    (comp (ref "C5")
      (value "22nF")
      (footprint "eagle-import:0603")
      (fields (field (name "PARTNO") "GRM188R71E223KA01D"))
      (libsource (lib "eagle-import") (part "CAPACITOR0603"))
    )
    (comp (ref "Q2")
      (value "SI2319DDS-T1-GE3")
      (footprint "eagle-import:SOT23")
      (libsource (lib "eagle-import") (part "BSS84"))
    )
    (comp (ref "R1")
      (value "10k")
      (footprint "eagle-import:0603")
      (fields (field (name "PARTNO") "RC0603JR-0710KL"))
      (libsource (lib "eagle-import") (part "RESISTOR0603"))
    )
    (comp (ref "U2")
      (value "L76L-M33")
      (footprint "eagle-import:GPS_MODULE")
      (fields (field (name "PARTNO") "L70B-M39"))
      (libsource (lib "eagle-import") (part "L70"))
    )
    (comp (ref "U10")
      (value "1575AT43A0040E")
      (footprint "eagle-import:1575AT43A0040E")
      (libsource (lib "eagle-import") (part "1575AT43A0040E"))
    )
    (comp (ref "Z1")
      (value "5.6nH")
      (footprint "eagle-import:0603")
      (fields (field (name "PARTNO") "‎GRM1885C1H120GA01D‎"))
      (libsource (lib "eagle-import") (part "RESISTOR0603"))
    )
    (comp (ref "Z2")
      (value "2.5pF")
      (footprint "eagle-import:0603")
      (fields (field (name "PARTNO") "‎GRM1885C1H120GA01D‎"))
      (libsource (lib "eagle-import") (part "RESISTOR0603"))
    )
    (comp (ref "Z3")
      (value "4pF")
      (footprint "eagle-import:0603")
      (fields (field (name "PARTNO") "‎GRM1885C1H120GA01D‎"))
      (libsource (lib "eagle-import") (part "RESISTOR0603"))
    )
  )
  (nets
    (net (code "1") (name "3.3V") (class "Default")
      (node (ref "3V3") (pin "TP") (pinfunction "TP_TP") (pintype "input"))
      (node (ref "C14") (pin "P$1") (pinfunction "1_P$1") (pintype "passive"))
      (node (ref "C15") (pin "P$1") (pinfunction "1_P$1") (pintype "passive"))
      (node (ref "C16") (pin "P$1") (pinfunction "1_P$1") (pintype "passive"))
      (node (ref "C17") (pin "P$1") (pinfunction "1_P$1") (pintype "passive"))
      (node (ref "C26") (pin "P$1") (pinfunction "1_P$1") (pintype "passive"))
      (node (ref "C28") (pin "P$1") (pinfunction "1_P$1") (pintype "passive"))
      (node (ref "C32") (pin "P$1") (pinfunction "1_P$1") (pintype "passive"))
      (node (ref "C34") (pin "P$1") (pinfunction "1_P$1") (pintype "passive"))
      (node (ref "C6") (pin "P$1") (pinfunction "1_P$1") (pintype "passive"))
      (node (ref "JLINK") (pin "5") (pinfunction "5_5") (pintype "passive"))
      (node (ref "L12") (pin "P$2") (pinfunction "2_P$2") (pintype "passive"))
      (node (ref "Q1") (pin "2") (pinfunction "S_2") (pintype "passive"))
      (node (ref "Q2") (pin "2") (pinfunction "S_2") (pintype "passive"))
      (node (ref "R1") (pin "P$2") (pinfunction "P$2_P$2") (pintype "passive"))
      (node (ref "R21") (pin "P$2") (pinfunction "P$2_P$2") (pintype "passive"))
      (node (ref "R22") (pin "P$2") (pinfunction "P$2_P$2") (pintype "passive"))
      (node (ref "U11") (pin "6") (pinfunction "VDD_1_6") (pintype "power_in"))
      (node (ref "U11") (pin "8") (pinfunction "VDD_2_8") (pintype "power_in"))
      (node (ref "U12") (pin "6") (pinfunction "VDD_1_6") (pintype "power_in"))
      (node (ref "U12") (pin "8") (pinfunction "VDD_2_8") (pintype "power_in"))
      (node (ref "U13") (pin "1") (pinfunction "VDD_1") (pintype "bidirectional"))
      (node (ref "U13") (pin "17") (pinfunction "VDD_17") (pintype "bidirectional"))
      (node (ref "U13") (pin "5") (pinfunction "VDDA_5") (pintype "bidirectional"))
      (node (ref "U15") (pin "4") (pinfunction "VCC_4") (pintype "bidirectional"))
      (node (ref "U2") (pin "P$6") (pinfunction "VBAT_P$6") (pintype "bidirectional"))
      (node (ref "U8") (pin "4") (pinfunction "VDD_4") (pintype "bidirectional"))
    )
    (net (code "2") (name "BOOT0") (class "Default")
      (node (ref "BOOT0") (pin "TP") (pinfunction "TP_TP") (pintype "input"))
      (node (ref "R23") (pin "P$1") (pinfunction "P$1_P$1") (pintype "passive"))
      (node (ref "U13") (pin "31") (pinfunction "BOOT0_31") (pintype "bidirectional"))
    )
    (net (code "3") (name "CS1") (class "Default")
      (node (ref "U11") (pin "15") (pinfunction "NSEL_15") (pintype "input"))
      (node (ref "U13") (pin "10") (pinfunction "PA4_10") (pintype "bidirectional"))
    )
    (net (code "4") (name "CS2") (class "Default")
      (node (ref "U12") (pin "15") (pinfunction "NSEL_15") (pintype "input"))
      (node (ref "U13") (pin "6") (pinfunction "PA0_6") (pintype "bidirectional"))
    )
    (net (code "5") (name "GND") (class "Default")
      (node (ref "C1") (pin "P$2") (pinfunction "2_P$2") (pintype "passive"))
      (node (ref "C11") (pin "P$2") (pinfunction "2_P$2") (pintype "passive"))
      (node (ref "C13") (pin "P$2") (pinfunction "2_P$2") (pintype "passive"))
      (node (ref "C14") (pin "P$2") (pinfunction "2_P$2") (pintype "passive"))
      (node (ref "C15") (pin "P$2") (pinfunction "2_P$2") (pintype "passive"))
      (node (ref "C16") (pin "P$2") (pinfunction "2_P$2") (pintype "passive"))
      (node (ref "C17") (pin "P$2") (pinfunction "2_P$2") (pintype "passive"))
      (node (ref "C21") (pin "P$2") (pinfunction "2_P$2") (pintype "passive"))
      (node (ref "C23") (pin "P$2") (pinfunction "2_P$2") (pintype "passive"))
      (node (ref "C26") (pin "P$2") (pinfunction "2_P$2") (pintype "passive"))
      (node (ref "C28") (pin "P$2") (pinfunction "2_P$2") (pintype "passive"))
      (node (ref "C3") (pin "P$2") (pinfunction "2_P$2") (pintype "passive"))
      (node (ref "C30") (pin "P$2") (pinfunction "2_P$2") (pintype "passive"))
      (node (ref "C32") (pin "P$2") (pinfunction "2_P$2") (pintype "passive"))
      (node (ref "C34") (pin "P$2") (pinfunction "2_P$2") (pintype "passive"))
      (node (ref "C36") (pin "P$2") (pinfunction "2_P$2") (pintype "passive"))
      (node (ref "C37") (pin "P$2") (pinfunction "2_P$2") (pintype "passive"))
      (node (ref "C39") (pin "P$2") (pinfunction "2_P$2") (pintype "passive"))
      (node (ref "C4") (pin "P$2") (pinfunction "2_P$2") (pintype "passive"))
      (node (ref "C42") (pin "P$2") (pinfunction "2_P$2") (pintype "passive"))
      (node (ref "C43") (pin "P$2") (pinfunction "2_P$2") (pintype "passive"))
      (node (ref "C47") (pin "P$2") (pinfunction "2_P$2") (pintype "passive"))
      (node (ref "C49") (pin "P$2") (pinfunction "2_P$2") (pintype "passive"))
      (node (ref "C5") (pin "P$2") (pinfunction "2_P$2") (pintype "passive"))
      (node (ref "C52") (pin "P$2") (pinfunction "2_P$2") (pintype "passive"))
      (node (ref "C53") (pin "P$2") (pinfunction "2_P$2") (pintype "passive"))
      (node (ref "C6") (pin "P$2") (pinfunction "2_P$2") (pintype "passive"))
      (node (ref "C7") (pin "P$2") (pinfunction "2_P$2") (pintype "passive"))
      (node (ref "C8") (pin "P$2") (pinfunction "2_P$2") (pintype "passive"))
      (node (ref "D3") (pin "C") (pinfunction "P$2_C") (pintype "bidirectional"))
      (node (ref "D4") (pin "A") (pinfunction "A_A") (pintype "passive"))
      (node (ref "GND1") (pin "TP") (pinfunction "TP_TP") (pintype "input"))
      (node (ref "GND2") (pin "TP") (pinfunction "TP_TP") (pintype "input"))
      (node (ref "J$1") (pin "GND@0") (pinfunction "GND_GND@0") (pintype "bidirectional"))
      (node (ref "J$1") (pin "GND@1") (pinfunction "GND_GND@1") (pintype "bidirectional"))
      (node (ref "J$1") (pin "GND@2") (pinfunction "GND_GND@2") (pintype "bidirectional"))
      (node (ref "J$1") (pin "GND@3") (pinfunction "GND_GND@3") (pintype "bidirectional"))
      (node (ref "JLINK") (pin "1") (pinfunction "1_1") (pintype "passive"))
      (node (ref "JP1") (pin "8") (pinfunction "8_8") (pintype "bidirectional"))
      (node (ref "L14") (pin "P$1") (pinfunction "1_P$1") (pintype "passive"))
      (node (ref "R12") (pin "P$1") (pinfunction "P$1_P$1") (pintype "passive"))
      (node (ref "R18") (pin "P$1") (pinfunction "P$1_P$1") (pintype "passive"))
      (node (ref "R23") (pin "P$2") (pinfunction "P$2_P$2") (pintype "passive"))
      (node (ref "R24") (pin "P$1") (pinfunction "P$1_P$1") (pintype "passive"))
      (node (ref "R4") (pin "P$1") (pinfunction "P$1_P$1") (pintype "passive"))
      (node (ref "S1") (pin "P$2") (pinfunction "S2_P$2") (pintype "bidirectional"))
      (node (ref "SWDIO1") (pin "TP") (pinfunction "TP_TP") (pintype "input"))
      (node (ref "SWDIO2") (pin "TP") (pinfunction "TP_TP") (pintype "input"))
      (node (ref "SWDIO3") (pin "TP") (pinfunction "TP_TP") (pintype "input"))
      (node (ref "SWDIO4") (pin "TP") (pinfunction "TP_TP") (pintype "input"))
      (node (ref "SWDIO5") (pin "TP") (pinfunction "TP_TP") (pintype "input"))
      (node (ref "SWDIO6") (pin "TP") (pinfunction "TP_TP") (pintype "input"))
      (node (ref "U1") (pin "2") (pinfunction "GND_2") (pintype "bidirectional"))
      (node (ref "U11") (pin "18") (pinfunction "GNDX_18") (pintype "bidirectional"))
      (node (ref "U11") (pin "3") (pinfunction "RXN_3") (pintype "input"))
      (node (ref "U11") (pin "5") (pinfunction "NC_5") (pintype "bidirectional"))
      (node (ref "U11") (pin "EXP") (pinfunction "PAD_EXP") (pintype "bidirectional"))
      (node (ref "U12") (pin "18") (pinfunction "GNDX_18") (pintype "bidirectional"))
      (node (ref "U12") (pin "3") (pinfunction "RXN_3") (pintype "input"))
      (node (ref "U12") (pin "5") (pinfunction "NC_5") (pintype "bidirectional"))
      (node (ref "U12") (pin "EXP") (pinfunction "PAD_EXP") (pintype "bidirectional"))
      (node (ref "U13") (pin "16") (pinfunction "VSS_16") (pintype "bidirectional"))
      (node (ref "U13") (pin "32") (pinfunction "VSS_32") (pintype "bidirectional"))
      (node (ref "U13") (pin "EXP") (pinfunction "PAD_EXP") (pintype "bidirectional"))
      (node (ref "U14") (pin "1") (pinfunction "S_1") (pintype "bidirectional"))
      (node (ref "U14") (pin "4") (pinfunction "S_4") (pintype "bidirectional"))
      (node (ref "U15") (pin "2") (pinfunction "GND_2") (pintype "bidirectional"))
      (node (ref "U15") (pin "5") (pinfunction "WP_5") (pintype "bidirectional"))
      (node (ref "U17") (pin "1") (pinfunction "S_1") (pintype "bidirectional"))
      (node (ref "U17") (pin "4") (pinfunction "S_4") (pintype "bidirectional"))
      (node (ref "U2") (pin "P$1") (pinfunction "GND_P$1") (pintype "bidirectional"))
      (node (ref "U2") (pin "P$10") (pinfunction "GND_P$10") (pintype "bidirectional"))
      (node (ref "U2") (pin "P$12") (pinfunction "GND_P$12") (pintype "bidirectional"))
      (node (ref "U3") (pin "P$4") (pinfunction "GND_P$4") (pintype "bidirectional"))
      (node (ref "U3") (pin "P$7") (pinfunction "GND_P$7") (pintype "bidirectional"))
      (node (ref "U5") (pin "2") (pinfunction "GND_2") (pintype "bidirectional"))
      (node (ref "U5") (pin "4") (pinfunction "GND_4") (pintype "bidirectional"))
      (node (ref "U5") (pin "5") (pinfunction "GND_5") (pintype "bidirectional"))
      (node (ref "U6") (pin "3") (pinfunction "P$3_3") (pintype "bidirectional"))
      (node (ref "U7") (pin "2") (pinfunction "S_2") (pintype "passive"))
      (node (ref "U7") (pin "2@1") (pinfunction "PAD_2@1") (pintype "bidirectional"))
      (node (ref "U8") (pin "2") (pinfunction "GND_2") (pintype "bidirectional"))
      (node (ref "U9") (pin "P$3") (pinfunction "GND_P$3") (pintype "bidirectional"))
      (node (ref "X1") (pin "2") (pinfunction "G2_2") (pintype "power_in"))
      (node (ref "X1") (pin "4") (pinfunction "G1_4") (pintype "power_in"))
      (node (ref "X2") (pin "2") (pinfunction "G2_2") (pintype "power_in"))
      (node (ref "X2") (pin "4") (pinfunction "G1_4") (pintype "power_in"))
      (node (ref "Z2") (pin "P$1") (pinfunction "P$1_P$1") (pintype "passive"))
      (node (ref "Z3") (pin "P$1") (pinfunction "P$1_P$1") (pintype "passive"))
    )
    (net (code "6") (name "GPS_1PPS") (class "Default")
      (node (ref "U13") (pin "8") (pinfunction "PA2_8") (pintype "bidirectional"))
      (node (ref "U2") (pin "P$4") (pinfunction "1PPS_P$4") (pintype "bidirectional"))
    )
    (net (code "7") (name "GPS_EN") (class "Default")
      (node (ref "Q2") (pin "1") (pinfunction "G_1") (pintype "passive"))
      (node (ref "R1") (pin "P$1") (pinfunction "P$1_P$1") (pintype "passive"))
      (node (ref "U13") (pin "2") (pinfunction "OSC_IN/PC14_2") (pintype "bidirectional"))
    )
    (net (code "8") (name "GPS_STATUS") (class "Default")
      (node (ref "U13") (pin "21") (pinfunction "PA11_21") (pintype "bidirectional"))
      (node (ref "U14") (pin "5") (pinfunction "G_5") (pintype "bidirectional"))
    )
    (net (code "9") (name "GPS_UART_TX") (class "Default")
      (node (ref "U13") (pin "9") (pinfunction "PA3_9") (pintype "bidirectional"))
      (node (ref "U2") (pin "P$2") (pinfunction "TX_P$2") (pintype "bidirectional"))
    )
    (net (code "10") (name "HOST_GPS_STATUS") (class "Default")
      (node (ref "JP1") (pin "4") (pinfunction "4_4") (pintype "bidirectional"))
      (node (ref "R14") (pin "P$2") (pinfunction "P$2_P$2") (pintype "passive"))
      (node (ref "U9") (pin "P$2") (pinfunction "C2_P$2") (pintype "bidirectional"))
    )
    (net (code "11") (name "HOST_RX_STATUS") (class "Default")
      (node (ref "JP1") (pin "6") (pinfunction "6_6") (pintype "bidirectional"))
      (node (ref "R15") (pin "P$2") (pinfunction "P$2_P$2") (pintype "passive"))
      (node (ref "U9") (pin "P$7") (pinfunction "C6_P$7") (pintype "bidirectional"))
    )
    (net (code "12") (name "HOST_TX_OFF") (class "Default")
      (node (ref "JP1") (pin "2") (pinfunction "2_2") (pintype "bidirectional"))
      (node (ref "R18") (pin "P$2") (pinfunction "P$2_P$2") (pintype "passive"))
      (node (ref "U17") (pin "2") (pinfunction "G_2") (pintype "bidirectional"))
      (node (ref "U9") (pin "P$1") (pinfunction "C1_P$1") (pintype "bidirectional"))
    )
    (net (code "13") (name "HOST_TX_STATUS") (class "Default")
      (node (ref "JP1") (pin "7") (pinfunction "7_7") (pintype "bidirectional"))
      (node (ref "R17") (pin "P$2") (pinfunction "P$2_P$2") (pintype "passive"))
      (node (ref "U9") (pin "P$6") (pinfunction "C5_P$6") (pintype "bidirectional"))
    )
    (net (code "14") (name "HOST_UART_RX") (class "Default")
      (node (ref "JP1") (pin "5") (pinfunction "5_5") (pintype "bidirectional"))
      (node (ref "R13") (pin "P$2") (pinfunction "P$2_P$2") (pintype "passive"))
      (node (ref "U9") (pin "P$8") (pinfunction "C7_P$8") (pintype "bidirectional"))
    )
    (net (code "15") (name "HOST_UART_TX") (class "Default")
      (node (ref "JP1") (pin "3") (pinfunction "3_3") (pintype "bidirectional"))
      (node (ref "R2") (pin "P$2") (pinfunction "P$2_P$2") (pintype "passive"))
      (node (ref "U9") (pin "P$9") (pinfunction "C8_P$9") (pintype "bidirectional"))
    )
    (net (code "16") (name "I2C_SCL") (class "Default")
      (node (ref "U13") (pin "29") (pinfunction "PB6_29") (pintype "bidirectional"))
      (node (ref "U15") (pin "1") (pinfunction "SCL_1") (pintype "bidirectional"))
    )
    (net (code "17") (name "I2C_SDA") (class "Default")
      (node (ref "U13") (pin "30") (pinfunction "PB7_30") (pintype "bidirectional"))
      (node (ref "U15") (pin "3") (pinfunction "SDA_3") (pintype "bidirectional"))
    )
    (net (code "18") (name "MCU_TX_OFF") (class "Default")
      (node (ref "U13") (pin "22") (pinfunction "PA12_22") (pintype "bidirectional"))
      (node (ref "U17") (pin "6") (pinfunction "D_6") (pintype "bidirectional"))
    )
    (net (code "19") (name "MCU_UART_RX") (class "Default")
      (node (ref "R2") (pin "P$1") (pinfunction "P$1_P$1") (pintype "passive"))
      (node (ref "RX") (pin "TP") (pinfunction "TP_TP") (pintype "input"))
      (node (ref "U13") (pin "20") (pinfunction "PA10_20") (pintype "bidirectional"))
      (node (ref "U6") (pin "1") (pinfunction "P$1_1") (pintype "bidirectional"))
    )
    (net (code "20") (name "MCU_UART_TX") (class "Default")
      (node (ref "R13") (pin "P$1") (pinfunction "P$1_P$1") (pintype "passive"))
      (node (ref "TX") (pin "TP") (pinfunction "TP_TP") (pintype "input"))
      (node (ref "U13") (pin "19") (pinfunction "PA9_19") (pintype "bidirectional"))
      (node (ref "U6") (pin "2") (pinfunction "P$2_2") (pintype "bidirectional"))
    )
    (net (code "21") (name "MISO") (class "Default")
      (node (ref "U11") (pin "13") (pinfunction "SDO_13") (pintype "output"))
      (node (ref "U12") (pin "13") (pinfunction "SDO_13") (pintype "output"))
      (node (ref "U13") (pin "12") (pinfunction "PA6_12") (pintype "bidirectional"))
    )
    (net (code "22") (name "MOSI") (class "Default")
      (node (ref "U11") (pin "14") (pinfunction "SDI_14") (pintype "input"))
      (node (ref "U12") (pin "14") (pinfunction "SDI_14") (pintype "input"))
      (node (ref "U13") (pin "13") (pinfunction "PA7_13") (pintype "bidirectional"))
    )
    (net (code "23") (name "NRST") (class "Default")
      (node (ref "JLINK") (pin "2") (pinfunction "2_2") (pintype "passive"))
      (node (ref "NRST") (pin "TP") (pinfunction "TP_TP") (pintype "input"))
      (node (ref "S1") (pin "P$1") (pinfunction "S1_P$1") (pintype "bidirectional"))
      (node (ref "U13") (pin "4") (pinfunction "NRST_4") (pintype "bidirectional"))
    )
    (net (code "24") (name "Net-(C1-1)") (class "Default")
      (node (ref "C1") (pin "P$1") (pinfunction "1_P$1") (pintype "passive"))
      (node (ref "C43") (pin "P$1") (pinfunction "1_P$1") (pintype "passive"))
      (node (ref "L2") (pin "P$2") (pinfunction "2_P$2") (pintype "passive"))
      (node (ref "U1") (pin "4") (pinfunction "EN_4") (pintype "bidirectional"))
      (node (ref "U1") (pin "5") (pinfunction "IN_5") (pintype "bidirectional"))
    )
    (net (code "25") (name "Net-(C2-1)") (class "Default")
      (node (ref "C2") (pin "P$1") (pinfunction "1_P$1") (pintype "passive"))
      (node (ref "U1") (pin "1") (pinfunction "BS_1") (pintype "bidirectional"))
    )
    (net (code "26") (name "Net-(C2-2)") (class "Default")
      (node (ref "C2") (pin "P$2") (pinfunction "2_P$2") (pintype "passive"))
      (node (ref "D4") (pin "C") (pinfunction "C_C") (pintype "passive"))
      (node (ref "L12") (pin "P$1") (pinfunction "1_P$1") (pintype "passive"))
      (node (ref "U1") (pin "6") (pinfunction "SW_6") (pintype "bidirectional"))
    )
    (net (code "27") (name "Net-(C3-1)") (class "Default")
      (node (ref "C3") (pin "P$1") (pinfunction "1_P$1") (pintype "passive"))
      (node (ref "C5") (pin "P$1") (pinfunction "1_P$1") (pintype "passive"))
      (node (ref "Q2") (pin "3") (pinfunction "D_3") (pintype "passive"))
      (node (ref "U2") (pin "P$8") (pinfunction "VCC_P$8") (pintype "bidirectional"))
    )
    (net (code "28") (name "Net-(C9-1)") (class "Default")
      (node (ref "C9") (pin "P$1") (pinfunction "1_P$1") (pintype "passive"))
      (node (ref "L8") (pin "P$2") (pinfunction "2_P$2") (pintype "passive"))
    )
    (net (code "29") (name "Net-(C10-1)") (class "Default")
      (node (ref "C10") (pin "P$1") (pinfunction "1_P$1") (pintype "passive"))
      (node (ref "C8") (pin "P$1") (pinfunction "1_P$1") (pintype "passive"))
      (node (ref "C9") (pin "P$2") (pinfunction "2_P$2") (pintype "passive"))
      (node (ref "L14") (pin "P$2") (pinfunction "2_P$2") (pintype "passive"))
    )
    (net (code "30") (name "Net-(C10-2)") (class "Default")
      (node (ref "C10") (pin "P$2") (pinfunction "2_P$2") (pintype "passive"))
      (node (ref "L13") (pin "P$1") (pinfunction "1_P$1") (pintype "passive"))
    )
    (net (code "31") (name "Net-(C12-1)") (class "Default")
      (node (ref "C12") (pin "P$1") (pinfunction "1_P$1") (pintype "passive"))
      (node (ref "L13") (pin "P$2") (pinfunction "2_P$2") (pintype "passive"))
    )
    (net (code "32") (name "Net-(C12-2)") (class "Default")
      (node (ref "C12") (pin "P$2") (pinfunction "2_P$2") (pintype "passive"))
      (node (ref "U5") (pin "6") (pinfunction "IN_6") (pintype "bidirectional"))
    )
    (net (code "33") (name "Net-(C13-1)") (class "Default")
      (node (ref "C13") (pin "P$1") (pinfunction "1_P$1") (pintype "passive"))
      (node (ref "R10") (pin "P$2") (pinfunction "P$2_P$2") (pintype "passive"))
      (node (ref "U5") (pin "1") (pinfunction "VCC_1") (pintype "bidirectional"))
    )
    (net (code "34") (name "Net-(C18-1)") (class "Default")
      (node (ref "C18") (pin "P$1") (pinfunction "1_P$1") (pintype "passive"))
      (node (ref "U5") (pin "3") (pinfunction "OUT_3") (pintype "bidirectional"))
    )
    (net (code "35") (name "Net-(C21-1)") (class "Default")
      (node (ref "C21") (pin "P$1") (pinfunction "1_P$1") (pintype "passive"))
      (node (ref "L5") (pin "P$1") (pinfunction "1_P$1") (pintype "passive"))
      (node (ref "R22") (pin "P$1") (pinfunction "P$1_P$1") (pintype "passive"))
    )
    (net (code "36") (name "Net-(C22-1)") (class "Default")
      (node (ref "C22") (pin "P$1") (pinfunction "1_P$1") (pintype "passive"))
      (node (ref "L5") (pin "P$2") (pinfunction "2_P$2") (pintype "passive"))
      (node (ref "U11") (pin "4") (pinfunction "TX_4") (pintype "output"))
    )
    (net (code "37") (name "Net-(C22-2)") (class "Default")
      (node (ref "C22") (pin "P$2") (pinfunction "2_P$2") (pintype "passive"))
      (node (ref "L1") (pin "P$1") (pinfunction "1_P$1") (pintype "passive"))
    )
    (net (code "38") (name "Net-(C23-1)") (class "Default")
      (node (ref "C23") (pin "P$1") (pinfunction "1_P$1") (pintype "passive"))
      (node (ref "L1") (pin "P$2") (pinfunction "2_P$2") (pintype "passive"))
      (node (ref "L6") (pin "P$1") (pinfunction "1_P$1") (pintype "passive"))
    )
    (net (code "39") (name "Net-(C29-2)") (class "Default")
      (node (ref "C29") (pin "P$2") (pinfunction "2_P$2") (pintype "passive"))
      (node (ref "C30") (pin "P$1") (pinfunction "1_P$1") (pintype "passive"))
      (node (ref "L3") (pin "P$1") (pinfunction "1_P$1") (pintype "passive"))
    )
    (net (code "40") (name "Net-(C36-1)") (class "Default")
      (node (ref "C36") (pin "P$1") (pinfunction "1_P$1") (pintype "passive"))
      (node (ref "L10") (pin "P$1") (pinfunction "1_P$1") (pintype "passive"))
      (node (ref "L9") (pin "P$2") (pinfunction "2_P$2") (pintype "passive"))
    )
    (net (code "41") (name "Net-(C37-1)") (class "Default")
      (node (ref "C37") (pin "P$1") (pinfunction "1_P$1") (pintype "passive"))
      (node (ref "C39") (pin "P$1") (pinfunction "1_P$1") (pintype "passive"))
      (node (ref "L4") (pin "P$2") (pinfunction "2_P$2") (pintype "passive"))
      (node (ref "L9") (pin "P$1") (pinfunction "1_P$1") (pintype "passive"))
      (node (ref "U7") (pin "3") (pinfunction "D_3") (pintype "passive"))
    )
    (net (code "42") (name "Net-(C42-1)") (class "Default")
      (node (ref "C42") (pin "P$1") (pinfunction "1_P$1") (pintype "passive"))
      (node (ref "C52") (pin "P$1") (pinfunction "1_P$1") (pintype "passive"))
      (node (ref "L10") (pin "P$2") (pinfunction "2_P$2") (pintype "passive"))
      (node (ref "L23") (pin "P$1") (pinfunction "1_P$1") (pintype "passive"))
    )
    (net (code "43") (name "Net-(C44-1)") (class "Default")
      (node (ref "C44") (pin "P$1") (pinfunction "1_P$1") (pintype "passive"))
      (node (ref "C53") (pin "P$1") (pinfunction "1_P$1") (pintype "passive"))
      (node (ref "L23") (pin "P$2") (pinfunction "2_P$2") (pintype "passive"))
    )
    (net (code "44") (name "Net-(J$1-SIGNAL)") (class "Default")
      (node (ref "J$1") (pin "SIG") (pinfunction "SIGNAL_SIG") (pintype "bidirectional"))
      (node (ref "RF") (pin "TP") (pinfunction "TP_TP") (pintype "input"))
      (node (ref "U8") (pin "5") (pinfunction "RFIN_5") (pintype "bidirectional"))
    )
    (net (code "45") (name "Net-(L17-1)") (class "Default")
      (node (ref "L17") (pin "P$1") (pinfunction "1_P$1") (pintype "passive"))
      (node (ref "L3") (pin "P$2") (pinfunction "2_P$2") (pintype "passive"))
      (node (ref "U7") (pin "1") (pinfunction "G_1") (pintype "passive"))
    )
    (net (code "46") (name "Net-(Q1-D)") (class "Default")
      (node (ref "Q1") (pin "3") (pinfunction "D_3") (pintype "passive"))
      (node (ref "R10") (pin "P$1") (pinfunction "P$1_P$1") (pintype "passive"))
      (node (ref "V_LNA") (pin "TP") (pinfunction "TP_TP") (pintype "input"))
    )
    (net (code "47") (name "Net-(U1-FB)") (class "Default")
      (node (ref "R21") (pin "P$1") (pinfunction "P$1_P$1") (pintype "passive"))
      (node (ref "R24") (pin "P$2") (pinfunction "P$2_P$2") (pintype "passive"))
      (node (ref "U1") (pin "3") (pinfunction "FB_3") (pintype "bidirectional"))
    )
    (net (code "48") (name "Net-(U2-RFIN)") (class "Default")
      (node (ref "U2") (pin "P$11") (pinfunction "RFIN_P$11") (pintype "bidirectional"))
      (node (ref "Z1") (pin "P$2") (pinfunction "P$2_P$2") (pintype "passive"))
      (node (ref "Z3") (pin "P$2") (pinfunction "P$2_P$2") (pintype "passive"))
    )
    (net (code "49") (name "Net-(U3-ADJ)") (class "Default")
      (node (ref "R4") (pin "P$2") (pinfunction "P$2_P$2") (pintype "passive"))
      (node (ref "R5") (pin "P$1") (pinfunction "P$1_P$1") (pintype "passive"))
      (node (ref "U3") (pin "P$2") (pinfunction "ADJ_P$2") (pintype "bidirectional"))
    )
    (net (code "50") (name "Net-(U10-RF)") (class "Default")
      (node (ref "U10") (pin "P$1") (pinfunction "RF_P$1") (pintype "bidirectional"))
      (node (ref "Z1") (pin "P$1") (pinfunction "P$1_P$1") (pintype "passive"))
      (node (ref "Z2") (pin "P$2") (pinfunction "P$2_P$2") (pintype "passive"))
    )
    (net (code "51") (name "Net-(U11-XIN)") (class "Default")
      (node (ref "U11") (pin "17") (pinfunction "XIN_17") (pintype "input"))
      (node (ref "X1") (pin "3") (pinfunction "X2_3") (pintype "bidirectional"))
    )
    (net (code "52") (name "Net-(U11-XOUT)") (class "Default")
      (node (ref "U11") (pin "16") (pinfunction "XOUT_16") (pintype "bidirectional"))
      (node (ref "X1") (pin "1") (pinfunction "X1_1") (pintype "bidirectional"))
    )
    (net (code "53") (name "Net-(U12-XIN)") (class "Default")
      (node (ref "U12") (pin "17") (pinfunction "XIN_17") (pintype "input"))
      (node (ref "X2") (pin "3") (pinfunction "X2_3") (pintype "bidirectional"))
    )
    (net (code "54") (name "Net-(U12-XOUT)") (class "Default")
      (node (ref "U12") (pin "16") (pinfunction "XOUT_16") (pintype "bidirectional"))
      (node (ref "X2") (pin "1") (pinfunction "X1_1") (pintype "bidirectional"))
    )
    (net (code "55") (name "Net-(U14A-D)") (class "Default")
      (node (ref "R14") (pin "P$1") (pinfunction "P$1_P$1") (pintype "passive"))
      (node (ref "U14") (pin "3") (pinfunction "D_3") (pintype "bidirectional"))
    )
    (net (code "56") (name "Net-(U14B-D)") (class "Default")
      (node (ref "R15") (pin "P$1") (pinfunction "P$1_P$1") (pintype "passive"))
      (node (ref "U14") (pin "6") (pinfunction "D_6") (pintype "bidirectional"))
    )
    (net (code "57") (name "Net-(U17A-D)") (class "Default")
      (node (ref "R17") (pin "P$1") (pinfunction "P$1_P$1") (pintype "passive"))
      (node (ref "U17") (pin "3") (pinfunction "D_3") (pintype "bidirectional"))
    )
    (net (code "58") (name "PA_GATE_BIAS") (class "Default")
      (node (ref "C11") (pin "P$1") (pinfunction "1_P$1") (pintype "passive"))
      (node (ref "L17") (pin "P$2") (pinfunction "2_P$2") (pintype "passive"))
      (node (ref "R11") (pin "P$1") (pinfunction "P$1_P$1") (pintype "passive"))
      (node (ref "R12") (pin "P$2") (pinfunction "P$2_P$2") (pintype "passive"))
    )
    (net (code "59") (name "PA_IN") (class "Default")
      (node (ref "C29") (pin "P$1") (pinfunction "1_P$1") (pintype "passive"))
      (node (ref "L6") (pin "P$2") (pinfunction "2_P$2") (pintype "passive"))
    )
    (net (code "60") (name "PA_OUT") (class "Default")
      (node (ref "C44") (pin "P$2") (pinfunction "2_P$2") (pintype "passive"))
      (node (ref "U8") (pin "1") (pinfunction "RF2_1") (pintype "bidirectional"))
    )
    (net (code "61") (name "RFSW_CTRL") (class "Default")
      (node (ref "Q1") (pin "1") (pinfunction "G_1") (pintype "passive"))
      (node (ref "U11") (pin "20") (pinfunction "GPIO3_20") (pintype "bidirectional"))
      (node (ref "U8") (pin "6") (pinfunction "CTRL_6") (pintype "bidirectional"))
    )
    (net (code "62") (name "RF_IN") (class "Default")
      (node (ref "L8") (pin "P$1") (pinfunction "1_P$1") (pintype "passive"))
      (node (ref "U8") (pin "3") (pinfunction "RF1_3") (pintype "bidirectional"))
    )
    (net (code "63") (name "RX_IC_CLK") (class "Default")
      (node (ref "U12") (pin "20") (pinfunction "GPIO3_20") (pintype "bidirectional"))
      (node (ref "U13") (pin "26") (pinfunction "PB3_26") (pintype "bidirectional"))
    )
    (net (code "64") (name "RX_IC_DATA") (class "Default")
      (node (ref "U12") (pin "10") (pinfunction "GPIO1_10") (pintype "bidirectional"))
      (node (ref "U13") (pin "27") (pinfunction "PB4_27") (pintype "bidirectional"))
    )
    (net (code "65") (name "RX_IN") (class "Default")
      (node (ref "C18") (pin "P$2") (pinfunction "2_P$2") (pintype "passive"))
      (node (ref "U11") (pin "2") (pinfunction "RXP_2") (pintype "input"))
      (node (ref "U12") (pin "2") (pinfunction "RXP_2") (pintype "input"))
    )
    (net (code "66") (name "RX_STATUS") (class "Default")
      (node (ref "U13") (pin "7") (pinfunction "PA1_7") (pintype "bidirectional"))
      (node (ref "U14") (pin "2") (pinfunction "G_2") (pintype "bidirectional"))
    )
    (net (code "67") (name "SCK") (class "Default")
      (node (ref "U11") (pin "12") (pinfunction "SCLK_12") (pintype "input"))
      (node (ref "U12") (pin "12") (pinfunction "SCLK_12") (pintype "input"))
      (node (ref "U13") (pin "11") (pinfunction "PA5_11") (pintype "bidirectional"))
    )
    (net (code "68") (name "SDN1") (class "Default")
      (node (ref "U11") (pin "1") (pinfunction "SDN_1") (pintype "input"))
      (node (ref "U13") (pin "14") (pinfunction "PB0_14") (pintype "bidirectional"))
    )
    (net (code "69") (name "SDN2") (class "Default")
      (node (ref "U12") (pin "1") (pinfunction "SDN_1") (pintype "input"))
      (node (ref "U13") (pin "25") (pinfunction "PA15_25") (pintype "bidirectional"))
    )
    (net (code "70") (name "SWCLK") (class "Default")
      (node (ref "JLINK") (pin "3") (pinfunction "3_3") (pintype "passive"))
      (node (ref "SWCLK") (pin "TP") (pinfunction "TP_TP") (pintype "input"))
      (node (ref "U13") (pin "24") (pinfunction "PA14_24") (pintype "bidirectional"))
    )
    (net (code "71") (name "SWDIO") (class "Default")
      (node (ref "JLINK") (pin "4") (pinfunction "4_4") (pintype "passive"))
      (node (ref "SWDIO") (pin "TP") (pinfunction "TP_TP") (pintype "input"))
      (node (ref "U13") (pin "23") (pinfunction "PA13_23") (pintype "bidirectional"))
    )
    (net (code "72") (name "TRX_IC_CLOCK") (class "Default")
      (node (ref "U11") (pin "19") (pinfunction "GPIO2_19") (pintype "bidirectional"))
      (node (ref "U13") (pin "3") (pinfunction "OSC_OUT/PC15_3") (pintype "bidirectional"))
    )
    (net (code "73") (name "TRX_IC_DATA") (class "Default")
      (node (ref "U11") (pin "10") (pinfunction "GPIO1_10") (pintype "bidirectional"))
      (node (ref "U13") (pin "15") (pinfunction "PB1_15") (pintype "bidirectional"))
    )
    (net (code "74") (name "TX_STATUS") (class "Default")
      (node (ref "U13") (pin "28") (pinfunction "PB5_28") (pintype "bidirectional"))
      (node (ref "U17") (pin "5") (pinfunction "G_5") (pintype "bidirectional"))
    )
    (net (code "75") (name "V_IN") (class "Default")
      (node (ref "C4") (pin "P$1") (pinfunction "1_P$1") (pintype "passive"))
      (node (ref "C47") (pin "P$1") (pinfunction "1_P$1") (pintype "passive"))
      (node (ref "D3") (pin "A") (pinfunction "P$1_A") (pintype "bidirectional"))
      (node (ref "JP1") (pin "1") (pinfunction "1_1") (pintype "bidirectional"))
      (node (ref "L2") (pin "P$1") (pinfunction "1_P$1") (pintype "passive"))
      (node (ref "U3") (pin "P$5") (pinfunction "EN_P$5") (pintype "bidirectional"))
      (node (ref "U3") (pin "P$6") (pinfunction "VIN_P$6") (pintype "bidirectional"))
      (node (ref "V_IN") (pin "TP") (pinfunction "TP_TP") (pintype "input"))
    )
    (net (code "76") (name "V_PA") (class "Default")
      (node (ref "C49") (pin "P$1") (pinfunction "1_P$1") (pintype "passive"))
      (node (ref "C7") (pin "P$1") (pinfunction "1_P$1") (pintype "passive"))
      (node (ref "L4") (pin "P$1") (pinfunction "1_P$1") (pintype "passive"))
      (node (ref "R5") (pin "P$2") (pinfunction "P$2_P$2") (pintype "passive"))
      (node (ref "U3") (pin "P$1") (pinfunction "VOUT_P$1") (pintype "bidirectional"))
      (node (ref "V_PA") (pin "TP") (pinfunction "TP_TP") (pintype "input"))
    )
    (net (code "77") (name "V_PA_BIAS") (class "Default")
      (node (ref "R11") (pin "P$2") (pinfunction "P$2_P$2") (pintype "passive"))
      (node (ref "U13") (pin "18") (pinfunction "PA8_18") (pintype "bidirectional"))
    )
    (net (code "78") (name "unconnected-(S1-S1-PadP$4)") (class "Default")
      (node (ref "S1") (pin "P$4") (pinfunction "S1_P$4") (pintype "bidirectional"))
    )
    (net (code "79") (name "unconnected-(S1-S2-PadP$3)") (class "Default")
      (node (ref "S1") (pin "P$3") (pinfunction "S2_P$3") (pintype "bidirectional"))
    )
    (net (code "80") (name "unconnected-(U2-RX-PadP$3)") (class "Default")
      (node (ref "U2") (pin "P$3") (pinfunction "RX_P$3") (pintype "bidirectional"))
    )
    (net (code "81") (name "unconnected-(U2-VIO-PadP$7)") (class "Default")
      (node (ref "U2") (pin "P$7") (pinfunction "VIO_P$7") (pintype "bidirectional"))
    )
    (net (code "82") (name "unconnected-(U3-PG-PadP$3)") (class "Default")
      (node (ref "U3") (pin "P$3") (pinfunction "PG_P$3") (pintype "bidirectional"))
    )
    (net (code "83") (name "unconnected-(U9-C3-PadP$4)") (class "Default")
      (node (ref "U9") (pin "P$4") (pinfunction "C3_P$4") (pintype "bidirectional"))
    )
    (net (code "84") (name "unconnected-(U9-C4-PadP$5)") (class "Default")
      (node (ref "U9") (pin "P$5") (pinfunction "C4_P$5") (pintype "bidirectional"))
    )
    (net (code "85") (name "unconnected-(U10-PAD-PadP$2)") (class "Default")
      (node (ref "U10") (pin "P$2") (pinfunction "PAD_P$2") (pintype "no_connect"))
    )
    (net (code "86") (name "unconnected-(U11-GPIO0-Pad9)") (class "Default")
      (node (ref "U11") (pin "9") (pinfunction "GPIO0_9") (pintype "bidirectional"))
    )
    (net (code "87") (name "unconnected-(U11-NIRQ-Pad11)") (class "Default")
      (node (ref "U11") (pin "11") (pinfunction "NIRQ_11") (pintype "bidirectional"))
    )
    (net (code "88") (name "unconnected-(U11-TXRAMP-Pad7)") (class "Default")
      (node (ref "U11") (pin "7") (pinfunction "TXRAMP_7") (pintype "bidirectional"))
    )
    (net (code "89") (name "unconnected-(U12-GPIO0-Pad9)") (class "Default")
      (node (ref "U12") (pin "9") (pinfunction "GPIO0_9") (pintype "bidirectional"))
    )
    (net (code "90") (name "unconnected-(U12-GPIO2-Pad19)") (class "Default")
      (node (ref "U12") (pin "19") (pinfunction "GPIO2_19") (pintype "bidirectional"))
    )
    (net (code "91") (name "unconnected-(U12-NIRQ-Pad11)") (class "Default")
      (node (ref "U12") (pin "11") (pinfunction "NIRQ_11") (pintype "bidirectional"))
    )
    (net (code "92") (name "unconnected-(U12-TX-Pad4)") (class "Default")
      (node (ref "U12") (pin "4") (pinfunction "TX_4") (pintype "output"))
    )
    (net (code "93") (name "unconnected-(U12-TXRAMP-Pad7)") (class "Default")
      (node (ref "U12") (pin "7") (pinfunction "TXRAMP_7") (pintype "bidirectional"))
    )
  )
)
